# CM4_MotherBoard.net
KiCad netlist of a schematic drawn in Altium Designer
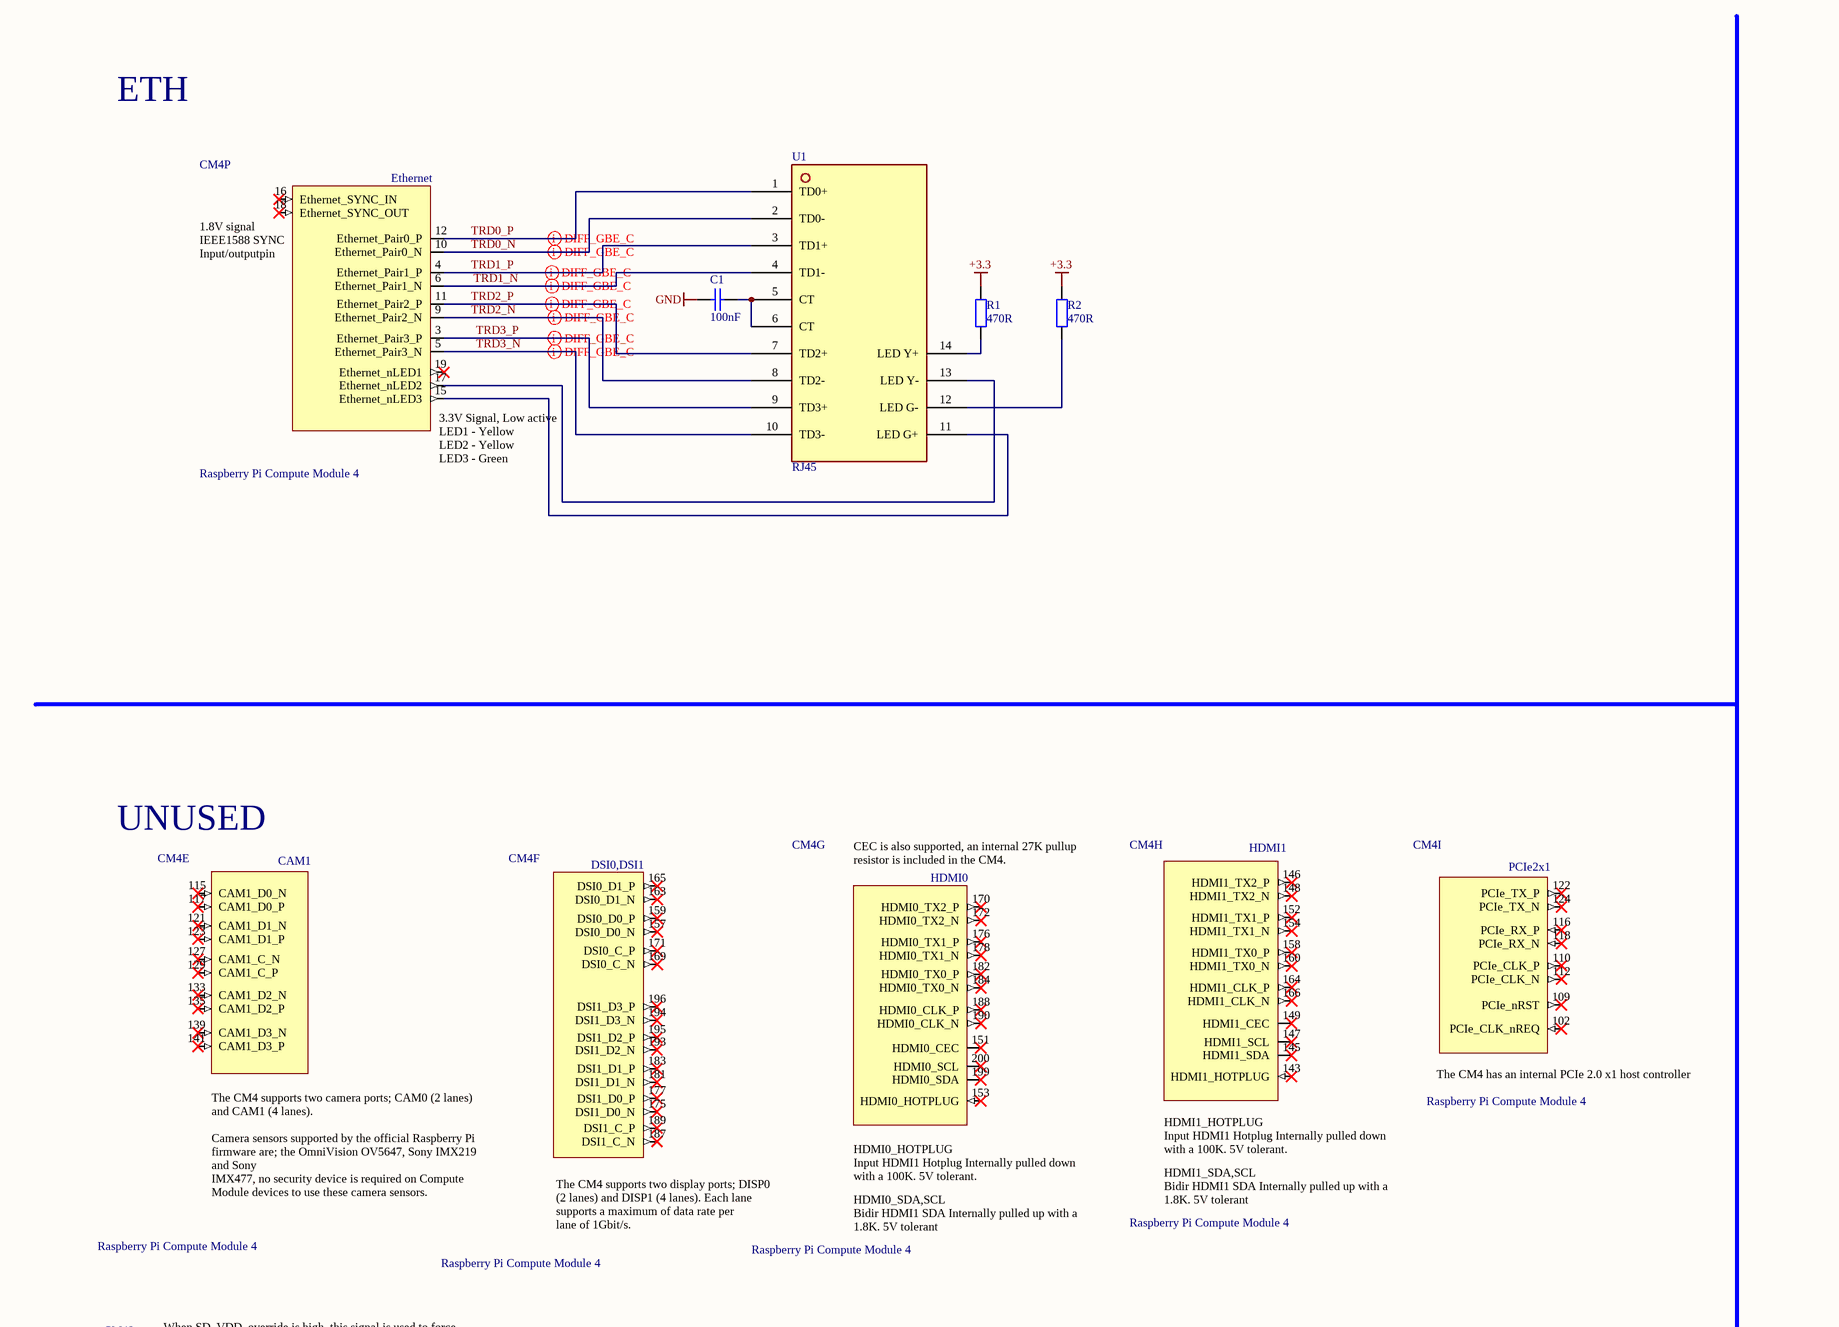
[diagram p0: CM4_MotherBoard.SchDoc, top left]
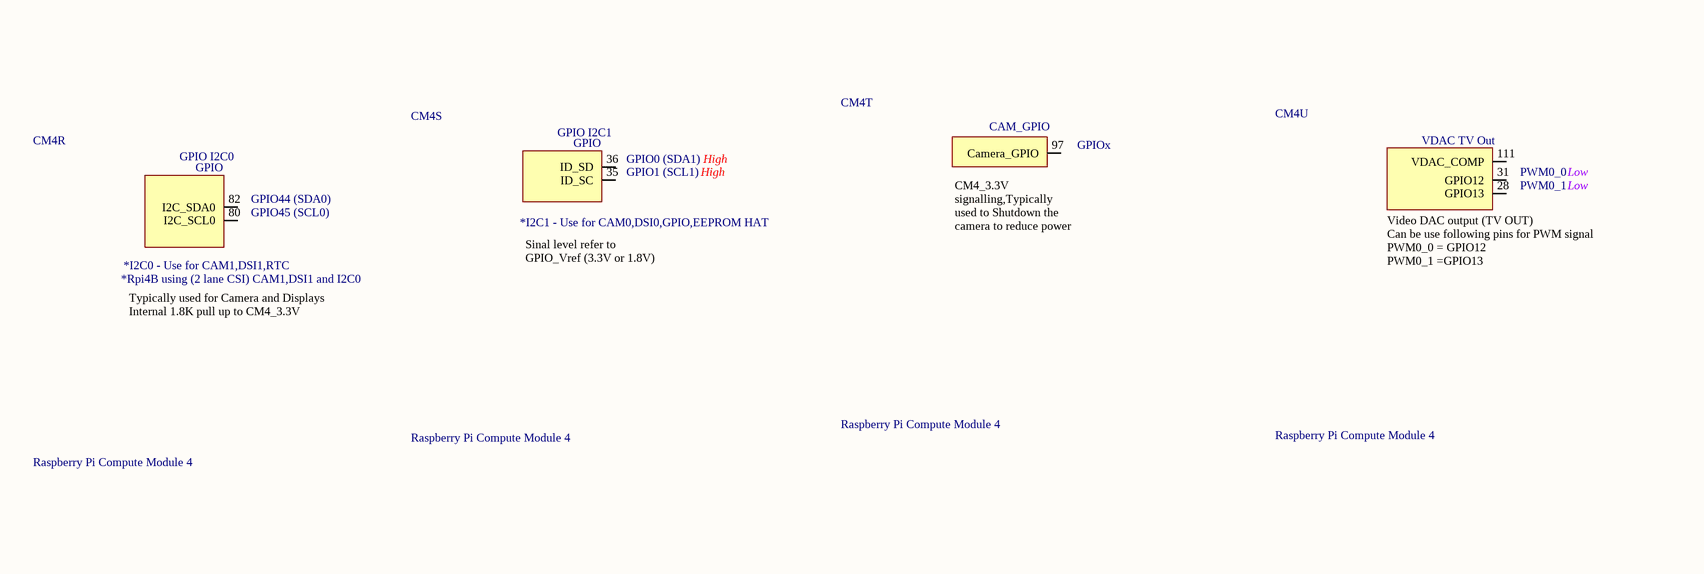
[diagram p1: CM4_MotherBoard.SchDoc, top middle]
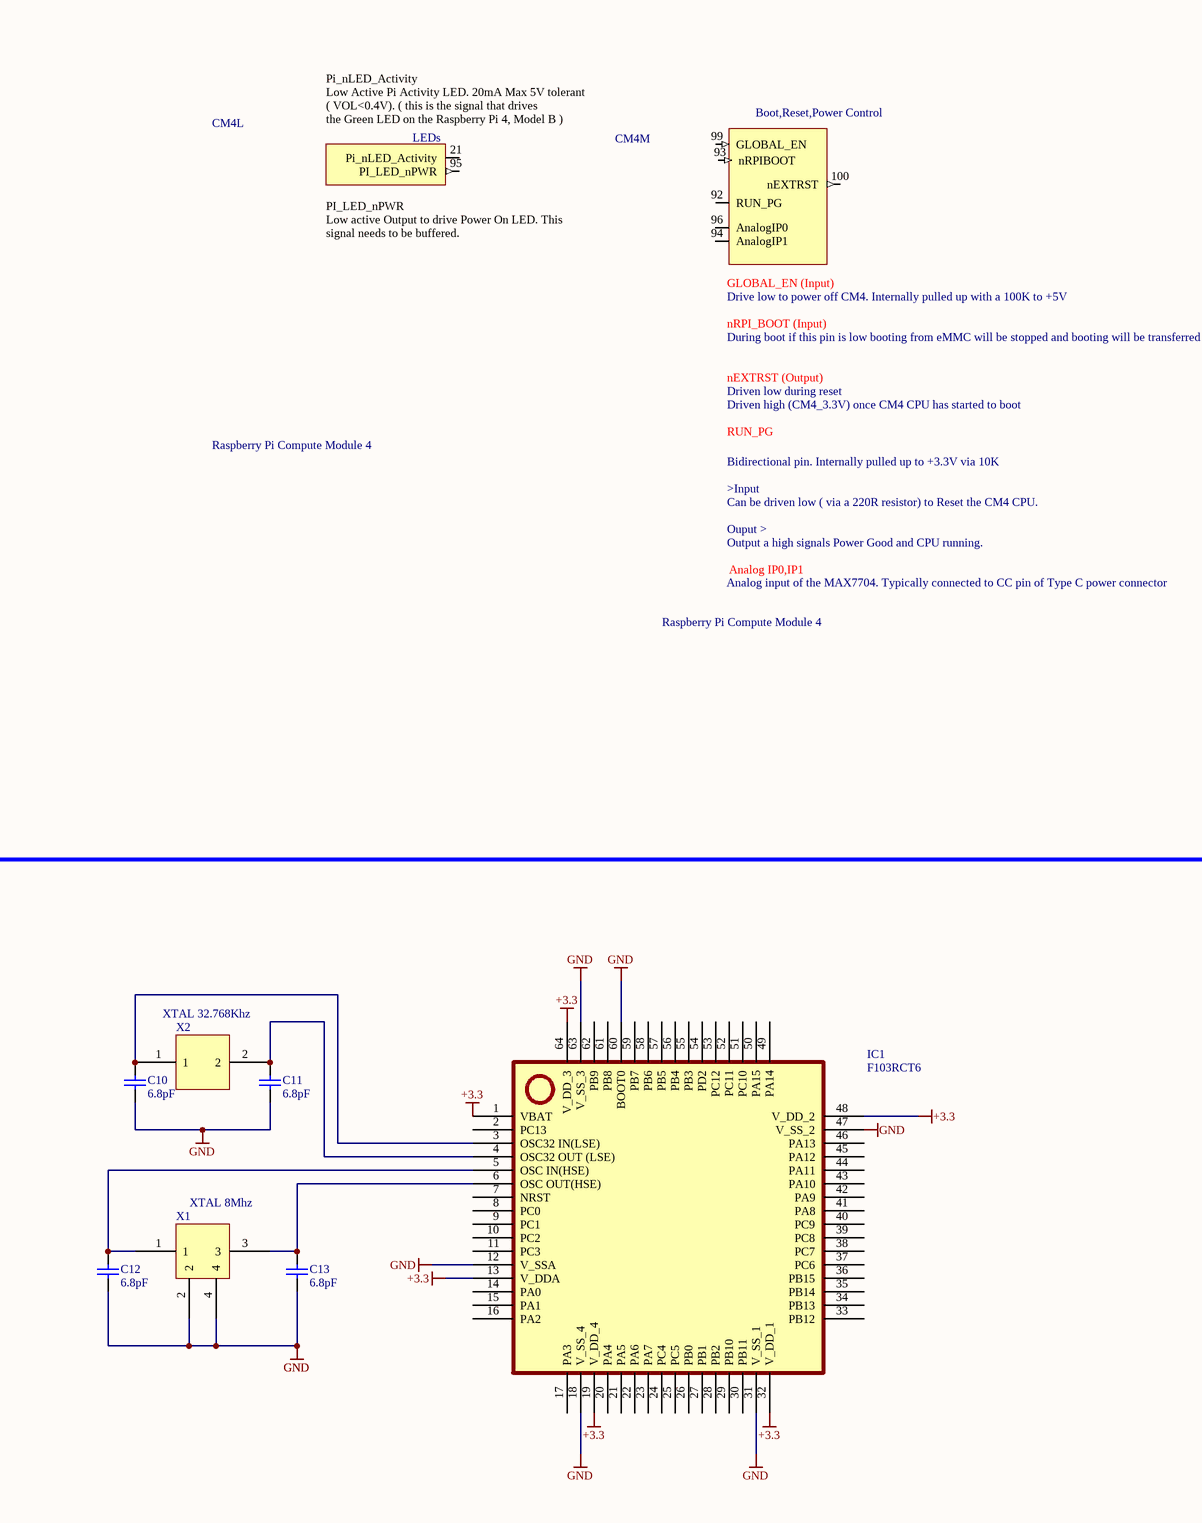
[diagram p2: CM4_MotherBoard.SchDoc, top right]
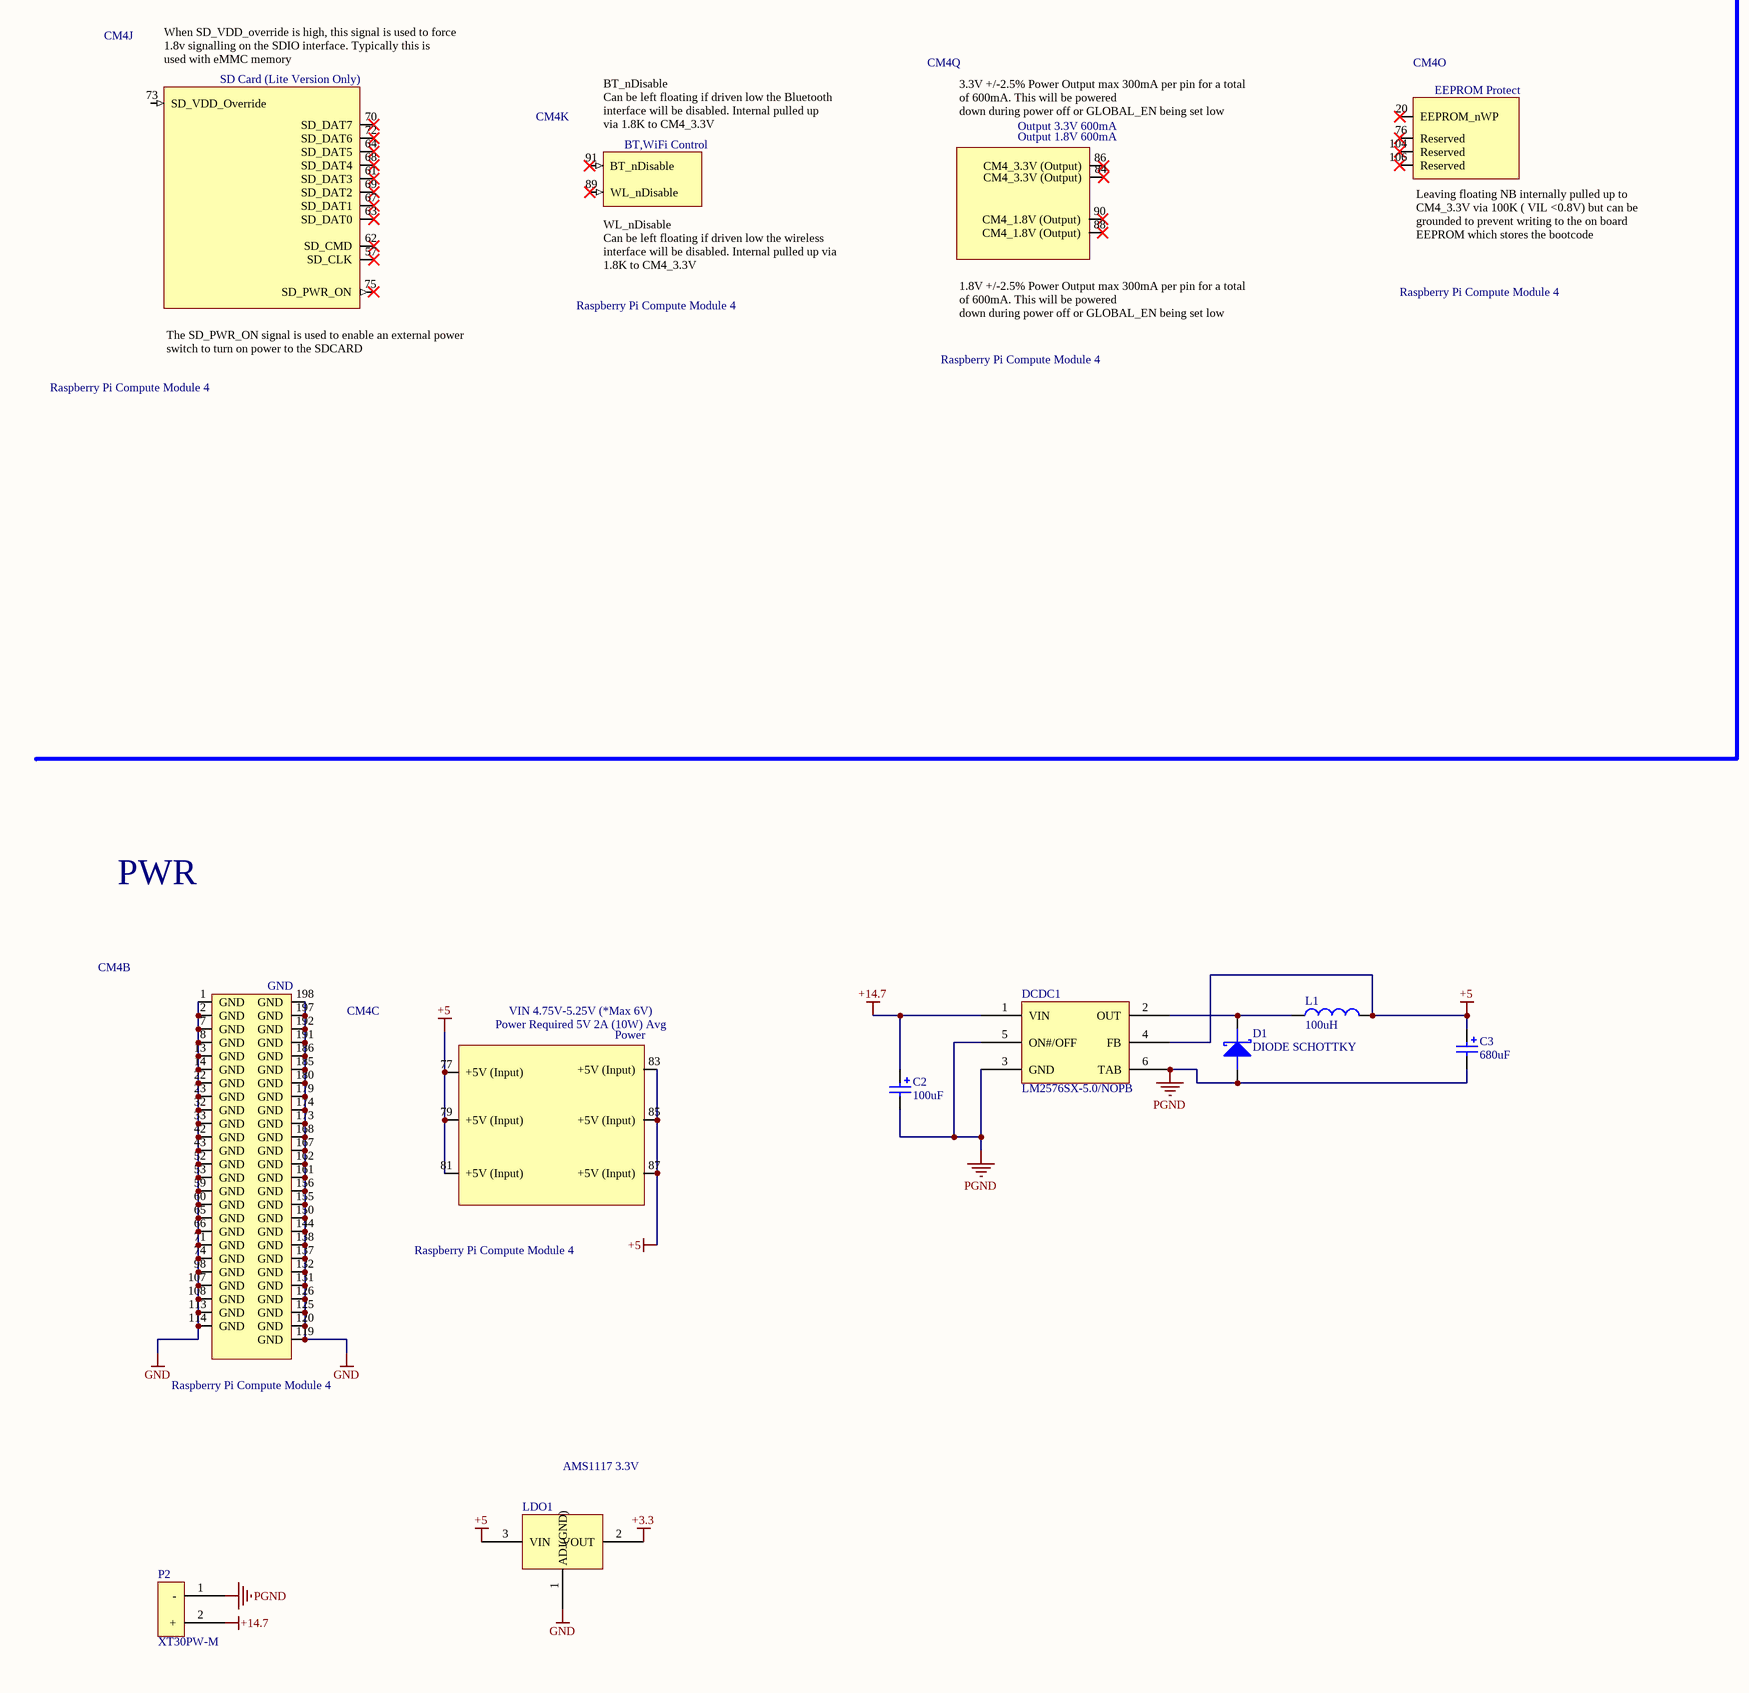
[diagram p3: CM4_MotherBoard.SchDoc, bottom left]
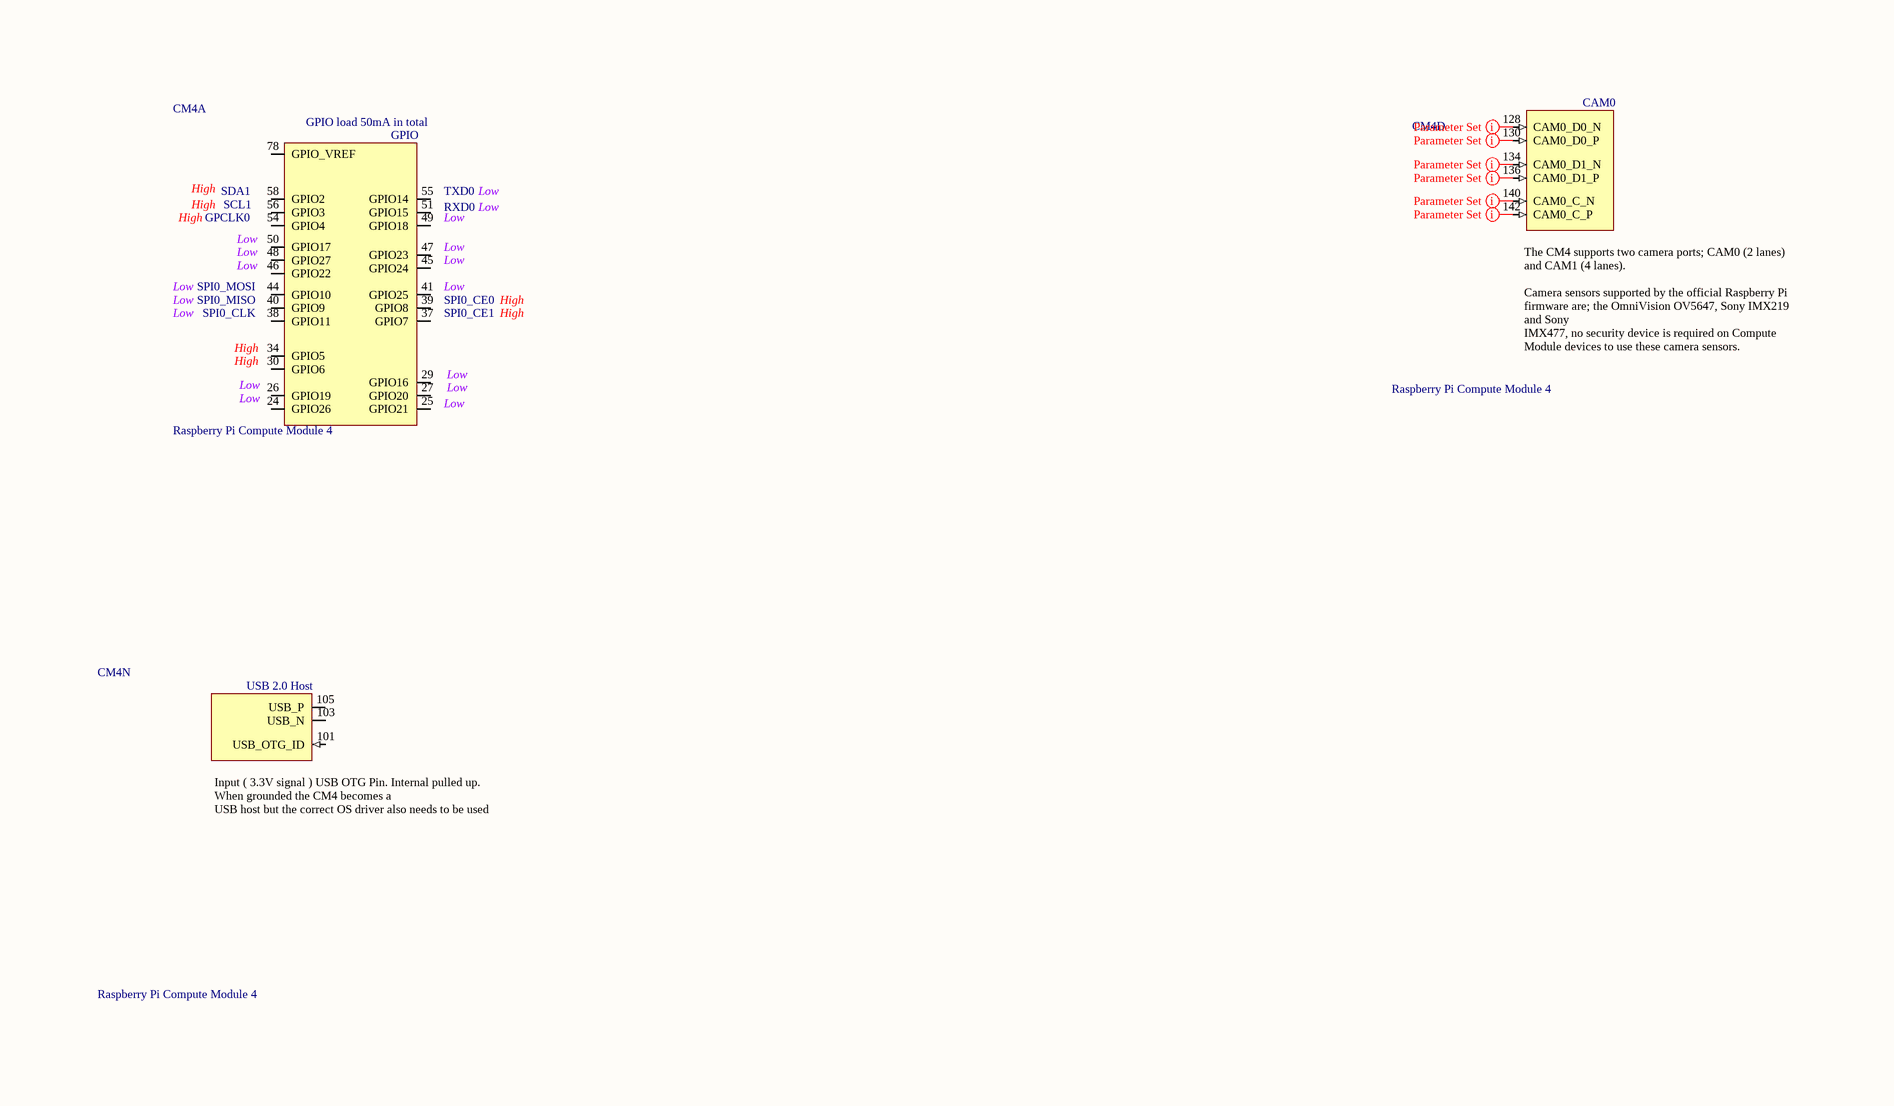
[diagram p4: CM4_MotherBoard.SchDoc, bottom middle]
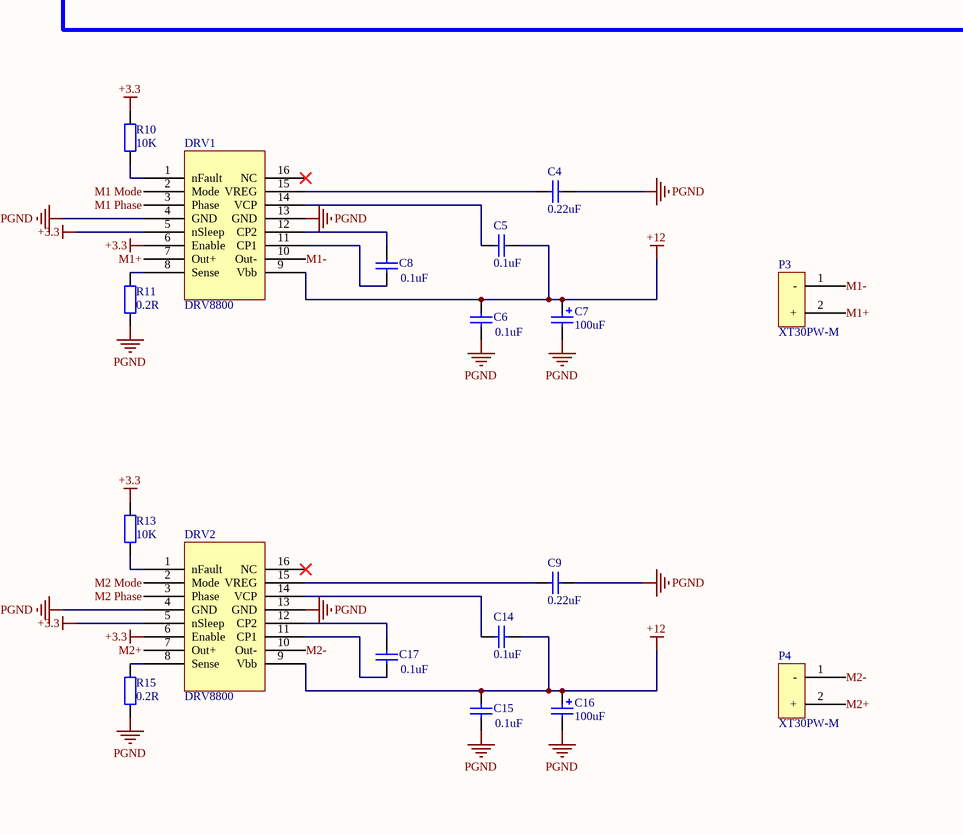
[diagram p5: CM4_MotherBoard.SchDoc, bottom right]

(export (version "E")
  (design (tool "Eeschema 10.0.6"))
  (components
    (comp (ref "C1")
      (value "100nF")
      (footprint "0805")
      (description "Capacitor")
      (fields (field (name "PUBLISHER") "Altium Limited"))
      (libsource (lib "CM4_Board") (part "Cap"))
    )
    (comp (ref "C2")
      (value "100uF")
      (footprint "Cap Pol 100uF")
      (description "Polarized Capacitor (Radial)")
      (fields (field (name "PUBLISHER") "Altium Limited"))
      (libsource (lib "CM4_Board") (part "Cap Pol"))
    )
    (comp (ref "C3")
      (value "680uF")
      (footprint "Cap Pol 680uF")
      (description "Polarized Capacitor (Radial)")
      (fields (field (name "PUBLISHER") "Altium Limited"))
      (libsource (lib "CM4_Board") (part "Cap Pol"))
    )
    (comp (ref "C4")
      (value "0.22uF")
      (footprint "0805")
      (description "Capacitor")
      (fields (field (name "PUBLISHER") "Altium Limited"))
      (libsource (lib "CM4_Board") (part "Cap"))
    )
    (comp (ref "C5")
      (value "0.1uF")
      (footprint "0805")
      (description "Capacitor")
      (fields (field (name "PUBLISHER") "Altium Limited"))
      (libsource (lib "CM4_Board") (part "Cap"))
    )
    (comp (ref "C6")
      (value "0.1uF")
      (footprint "0805")
      (description "Capacitor")
      (fields (field (name "PUBLISHER") "Altium Limited"))
      (libsource (lib "CM4_Board") (part "Cap"))
    )
    (comp (ref "C7")
      (value "100uF")
      (footprint "Cap Pol 680uF")
      (description "Polarized Capacitor (Radial)")
      (fields (field (name "PUBLISHER") "Altium Limited"))
      (libsource (lib "CM4_Board") (part "Cap Pol"))
    )
    (comp (ref "C8")
      (value "0.1uF")
      (footprint "0805")
      (description "Capacitor")
      (fields (field (name "PUBLISHER") "Altium Limited"))
      (libsource (lib "CM4_Board") (part "Cap"))
    )
    (comp (ref "C9")
      (value "0.22uF")
      (footprint "0805")
      (description "Capacitor")
      (fields (field (name "PUBLISHER") "Altium Limited"))
      (libsource (lib "CM4_Board") (part "Cap"))
    )
    (comp (ref "C10")
      (value "6.8pF")
      (footprint "0805")
      (description "Capacitor")
      (fields (field (name "PUBLISHER") "Altium Limited"))
      (libsource (lib "CM4_Board") (part "Cap"))
    )
    (comp (ref "C11")
      (value "6.8pF")
      (footprint "0805")
      (description "Capacitor")
      (fields (field (name "PUBLISHER") "Altium Limited"))
      (libsource (lib "CM4_Board") (part "Cap"))
    )
    (comp (ref "C12")
      (value "6.8pF")
      (footprint "0805")
      (description "Capacitor")
      (fields (field (name "PUBLISHER") "Altium Limited"))
      (libsource (lib "CM4_Board") (part "Cap"))
    )
    (comp (ref "C13")
      (value "6.8pF")
      (footprint "0805")
      (description "Capacitor")
      (fields (field (name "PUBLISHER") "Altium Limited"))
      (libsource (lib "CM4_Board") (part "Cap"))
    )
    (comp (ref "C14")
      (value "0.1uF")
      (footprint "0805")
      (description "Capacitor")
      (fields (field (name "PUBLISHER") "Altium Limited"))
      (libsource (lib "CM4_Board") (part "Cap"))
    )
    (comp (ref "C15")
      (value "0.1uF")
      (footprint "0805")
      (description "Capacitor")
      (fields (field (name "PUBLISHER") "Altium Limited"))
      (libsource (lib "CM4_Board") (part "Cap"))
    )
    (comp (ref "C16")
      (value "100uF")
      (footprint "Cap Pol 680uF")
      (description "Polarized Capacitor (Radial)")
      (fields (field (name "PUBLISHER") "Altium Limited"))
      (libsource (lib "CM4_Board") (part "Cap Pol"))
    )
    (comp (ref "C17")
      (value "0.1uF")
      (footprint "0805")
      (description "Capacitor")
      (fields (field (name "PUBLISHER") "Altium Limited"))
      (libsource (lib "CM4_Board") (part "Cap"))
    )
    (comp (ref "CM4")
      (value "Raspberry Pi Compute Module 4")
      (footprint "CM4-F40C-100DS-0.4v_1.5mm_0mm")
      (description "Raspberry Pi Compute Module 4 by Amornthep Phunsin")
      (libsource (lib "CM4") (part "CM4"))
    )
    (comp (ref "D1")
      (value "DIODE SCHOTTKY")
      (footprint "Schottky")
      (description "肖特基二极管")
      (libsource (lib "CM4_Board") (part "DIODE SCHOTTKY"))
    )
    (comp (ref "DCDC1")
      (value "LM2576SX-5.0/NOPB")
      (footprint "LM2576SX-5.0/NOPB")
      (libsource (lib "CM4_Board") (part "LM2576SX-5.0/NOPB"))
    )
    (comp (ref "DRV1") (value "DRV8800") (footprint "DRV8800") (libsource (lib "CM4_Board") (part "DRV8800")))
    (comp (ref "DRV2") (value "DRV8800") (footprint "DRV8800") (libsource (lib "CM4_Board") (part "DRV8800")))
    (comp (ref "IC1")
      (value "F103RCT6")
      (footprint "F103")
      (description "STM32F103RCT6 LQFP64")
      (libsource (lib "F103_Board") (part "F103RCT6"))
    )
    (comp (ref "L1")
      (value "100uH")
      (footprint "Inductor 100uH")
      (description "Inductor")
      (fields (field (name "PUBLISHER") "Altium Limited"))
      (libsource (lib "CM4_Board") (part "Inductor"))
    )
    (comp (ref "LDO1")
      (value "AMS1117 3.3V")
      (footprint "AMS117")
      (libsource (lib "CM4_Board") (part "AMS1117 3.3V"))
    )
    (comp (ref "P2")
      (value "XT30PW-M")
      (footprint "XT30PW-M")
      (libsource (lib "CM4_Board") (part "XT30PW-M"))
    )
    (comp (ref "P3")
      (value "XT30PW-M")
      (footprint "XT30PW-M")
      (libsource (lib "CM4_Board") (part "XT30PW-M"))
    )
    (comp (ref "P4")
      (value "XT30PW-M")
      (footprint "XT30PW-M")
      (libsource (lib "CM4_Board") (part "XT30PW-M"))
    )
    (comp (ref "R1")
      (value "470R")
      (footprint "0805")
      (description "Resistor")
      (fields (field (name "PUBLISHER") "Altium Limited"))
      (libsource (lib "CM4_Board") (part "Res"))
    )
    (comp (ref "R2")
      (value "470R")
      (footprint "0805")
      (description "Resistor")
      (fields (field (name "PUBLISHER") "Altium Limited"))
      (libsource (lib "CM4_Board") (part "Res"))
    )
    (comp (ref "R10")
      (value "10K")
      (footprint "0805")
      (description "Resistor")
      (fields (field (name "PUBLISHER") "Altium Limited"))
      (libsource (lib "CM4_Board") (part "Res"))
    )
    (comp (ref "R11")
      (value "0.2R")
      (footprint "0805")
      (description "Resistor")
      (fields (field (name "PUBLISHER") "Altium Limited"))
      (libsource (lib "CM4_Board") (part "Res"))
    )
    (comp (ref "R13")
      (value "10K")
      (footprint "0805")
      (description "Resistor")
      (fields (field (name "PUBLISHER") "Altium Limited"))
      (libsource (lib "CM4_Board") (part "Res"))
    )
    (comp (ref "R15")
      (value "0.2R")
      (footprint "0805")
      (description "Resistor")
      (fields (field (name "PUBLISHER") "Altium Limited"))
      (libsource (lib "CM4_Board") (part "Res"))
    )
    (comp (ref "U1")
      (value "RJ45")
      (footprint "RJ45")
      (description "48F-01GY2DPL2NL")
      (libsource (lib "CM4_Board") (part "RJ45"))
    )
    (comp (ref "X1")
      (value "XTAL 8Mhz")
      (footprint "XTAL 8Mhz")
      (description "8Mhz XTAL  SMD3225-4P")
      (libsource (lib "F103_Board") (part "XTAL 8Mhz"))
    )
    (comp (ref "X2")
      (value "XTAL 32.768Khz")
      (footprint "XTAL 32.768Khz")
      (description "32.768Khz XTAL  SMD3215-2P")
      (libsource (lib "F103_Board") (part "XTAL 32.768Khz"))
    )
  )
  (nets
    (net (code "1") (name "+3.3") (class "Default")
      (node (ref "DRV1") (pin "5") (pinfunction "nSleep_5") (pintype "passive"))
      (node (ref "DRV1") (pin "6") (pinfunction "Enable_6") (pintype "passive"))
      (node (ref "DRV2") (pin "5") (pinfunction "nSleep_5") (pintype "passive"))
      (node (ref "DRV2") (pin "6") (pinfunction "Enable_6") (pintype "passive"))
      (node (ref "IC1") (pin "1") (pinfunction "VBAT_1") (pintype "passive"))
      (node (ref "IC1") (pin "13") (pinfunction "V_DDA_13") (pintype "passive"))
      (node (ref "IC1") (pin "19") (pinfunction "V_DD_4_19") (pintype "passive"))
      (node (ref "IC1") (pin "32") (pinfunction "V_DD_1_32") (pintype "passive"))
      (node (ref "IC1") (pin "48") (pinfunction "V_DD_2_48") (pintype "passive"))
      (node (ref "IC1") (pin "64") (pinfunction "V_DD_3_64") (pintype "passive"))
      (node (ref "LDO1") (pin "2") (pinfunction "VOUT_2") (pintype "passive"))
      (node (ref "R1") (pin "2") (pinfunction "2_2") (pintype "passive"))
      (node (ref "R10") (pin "2") (pinfunction "2_2") (pintype "passive"))
      (node (ref "R13") (pin "2") (pinfunction "2_2") (pintype "passive"))
      (node (ref "R2") (pin "2") (pinfunction "2_2") (pintype "passive"))
    )
    (net (code "2") (name "+5") (class "Default")
      (node (ref "C3") (pin "1") (pinfunction "1_1") (pintype "passive"))
      (node (ref "CM4") (pin "77") (pinfunction "+5V_(Input)_77") (pintype "power_in"))
      (node (ref "CM4") (pin "79") (pinfunction "+5V_(Input)_79") (pintype "power_in"))
      (node (ref "CM4") (pin "81") (pinfunction "+5V_(Input)_81") (pintype "power_in"))
      (node (ref "CM4") (pin "83") (pinfunction "+5V_(Input)_83") (pintype "power_in"))
      (node (ref "CM4") (pin "85") (pinfunction "+5V_(Input)_85") (pintype "power_in"))
      (node (ref "CM4") (pin "87") (pinfunction "+5V_(Input)_87") (pintype "power_in"))
      (node (ref "DCDC1") (pin "4") (pinfunction "FB_4") (pintype "passive"))
      (node (ref "L1") (pin "2") (pinfunction "2_2") (pintype "passive"))
      (node (ref "LDO1") (pin "3") (pinfunction "VIN_3") (pintype "passive"))
    )
    (net (code "3") (name "+12") (class "Default")
      (node (ref "C14") (pin "2") (pinfunction "2_2") (pintype "passive"))
      (node (ref "C15") (pin "2") (pinfunction "2_2") (pintype "passive"))
      (node (ref "C16") (pin "1") (pinfunction "1_1") (pintype "passive"))
      (node (ref "C5") (pin "2") (pinfunction "2_2") (pintype "passive"))
      (node (ref "C6") (pin "2") (pinfunction "2_2") (pintype "passive"))
      (node (ref "C7") (pin "1") (pinfunction "1_1") (pintype "passive"))
      (node (ref "DRV1") (pin "9") (pinfunction "Vbb_9") (pintype "passive"))
      (node (ref "DRV2") (pin "9") (pinfunction "Vbb_9") (pintype "passive"))
    )
    (net (code "4") (name "+14.7") (class "Default")
      (node (ref "C2") (pin "1") (pinfunction "1_1") (pintype "passive"))
      (node (ref "DCDC1") (pin "1") (pinfunction "VIN_1") (pintype "passive"))
      (node (ref "P2") (pin "2") (pinfunction "+_2") (pintype "passive"))
    )
    (net (code "5") (name "/M1 Mode") (class "Default")
      (node (ref "DRV1") (pin "2") (pinfunction "Mode_2") (pintype "passive"))
    )
    (net (code "6") (name "/M1 Phase") (class "Default")
      (node (ref "DRV1") (pin "3") (pinfunction "Phase_3") (pintype "passive"))
    )
    (net (code "7") (name "/M1+") (class "Default")
      (node (ref "DRV1") (pin "7") (pinfunction "Out+_7") (pintype "passive"))
      (node (ref "P3") (pin "2") (pinfunction "+_2") (pintype "passive"))
    )
    (net (code "8") (name "/M1-") (class "Default")
      (node (ref "DRV1") (pin "10") (pinfunction "Out-_10") (pintype "passive"))
      (node (ref "P3") (pin "1") (pinfunction "-_1") (pintype "passive"))
    )
    (net (code "9") (name "/M2 Mode") (class "Default")
      (node (ref "DRV2") (pin "2") (pinfunction "Mode_2") (pintype "passive"))
    )
    (net (code "10") (name "/M2 Phase") (class "Default")
      (node (ref "DRV2") (pin "3") (pinfunction "Phase_3") (pintype "passive"))
    )
    (net (code "11") (name "/M2+") (class "Default")
      (node (ref "DRV2") (pin "7") (pinfunction "Out+_7") (pintype "passive"))
      (node (ref "P4") (pin "2") (pinfunction "+_2") (pintype "passive"))
    )
    (net (code "12") (name "/M2-") (class "Default")
      (node (ref "DRV2") (pin "10") (pinfunction "Out-_10") (pintype "passive"))
      (node (ref "P4") (pin "1") (pinfunction "-_1") (pintype "passive"))
    )
    (net (code "13") (name "/TRD0_N") (class "Default")
      (node (ref "CM4") (pin "10") (pinfunction "Ethernet_Pair0_N_10") (pintype "passive"))
      (node (ref "U1") (pin "2") (pinfunction "TD0-_2") (pintype "passive"))
    )
    (net (code "14") (name "/TRD0_P") (class "Default")
      (node (ref "CM4") (pin "12") (pinfunction "Ethernet_Pair0_P_12") (pintype "passive"))
      (node (ref "U1") (pin "1") (pinfunction "TD0+_1") (pintype "passive"))
    )
    (net (code "15") (name "/TRD1_N") (class "Default")
      (node (ref "CM4") (pin "6") (pinfunction "Ethernet_Pair1_N_6") (pintype "passive"))
      (node (ref "U1") (pin "4") (pinfunction "TD1-_4") (pintype "passive"))
    )
    (net (code "16") (name "/TRD1_P") (class "Default")
      (node (ref "CM4") (pin "4") (pinfunction "Ethernet_Pair1_P_4") (pintype "passive"))
      (node (ref "U1") (pin "3") (pinfunction "TD1+_3") (pintype "passive"))
    )
    (net (code "17") (name "/TRD2_N") (class "Default")
      (node (ref "CM4") (pin "9") (pinfunction "Ethernet_Pair2_N_9") (pintype "passive"))
      (node (ref "U1") (pin "8") (pinfunction "TD2-_8") (pintype "passive"))
    )
    (net (code "18") (name "/TRD2_P") (class "Default")
      (node (ref "CM4") (pin "11") (pinfunction "Ethernet_Pair2_P_11") (pintype "passive"))
      (node (ref "U1") (pin "7") (pinfunction "TD2+_7") (pintype "passive"))
    )
    (net (code "19") (name "/TRD3_N") (class "Default")
      (node (ref "CM4") (pin "5") (pinfunction "Ethernet_Pair3_N_5") (pintype "passive"))
      (node (ref "U1") (pin "10") (pinfunction "TD3-_10") (pintype "passive"))
    )
    (net (code "20") (name "/TRD3_P") (class "Default")
      (node (ref "CM4") (pin "3") (pinfunction "Ethernet_Pair3_P_3") (pintype "passive"))
      (node (ref "U1") (pin "9") (pinfunction "TD3+_9") (pintype "passive"))
    )
    (net (code "21") (name "GND") (class "Default")
      (node (ref "C1") (pin "1") (pinfunction "1_1") (pintype "passive"))
      (node (ref "C10") (pin "1") (pinfunction "1_1") (pintype "passive"))
      (node (ref "C11") (pin "1") (pinfunction "1_1") (pintype "passive"))
      (node (ref "C12") (pin "1") (pinfunction "1_1") (pintype "passive"))
      (node (ref "C13") (pin "1") (pinfunction "1_1") (pintype "passive"))
      (node (ref "CM4") (pin "1") (pinfunction "GND_1") (pintype "power_in"))
      (node (ref "CM4") (pin "107") (pinfunction "GND_107") (pintype "power_in"))
      (node (ref "CM4") (pin "108") (pinfunction "GND_108") (pintype "power_in"))
      (node (ref "CM4") (pin "113") (pinfunction "GND_113") (pintype "power_in"))
      (node (ref "CM4") (pin "114") (pinfunction "GND_114") (pintype "power_in"))
      (node (ref "CM4") (pin "119") (pinfunction "GND_119") (pintype "power_in"))
      (node (ref "CM4") (pin "120") (pinfunction "GND_120") (pintype "power_in"))
      (node (ref "CM4") (pin "125") (pinfunction "GND_125") (pintype "power_in"))
      (node (ref "CM4") (pin "126") (pinfunction "GND_126") (pintype "power_in"))
      (node (ref "CM4") (pin "13") (pinfunction "GND_13") (pintype "power_in"))
      (node (ref "CM4") (pin "131") (pinfunction "GND_131") (pintype "power_in"))
      (node (ref "CM4") (pin "132") (pinfunction "GND_132") (pintype "power_in"))
      (node (ref "CM4") (pin "137") (pinfunction "GND_137") (pintype "power_in"))
      (node (ref "CM4") (pin "138") (pinfunction "GND_138") (pintype "power_in"))
      (node (ref "CM4") (pin "14") (pinfunction "GND_14") (pintype "power_in"))
      (node (ref "CM4") (pin "144") (pinfunction "GND_144") (pintype "power_in"))
      (node (ref "CM4") (pin "150") (pinfunction "GND_150") (pintype "power_in"))
      (node (ref "CM4") (pin "155") (pinfunction "GND_155") (pintype "power_in"))
      (node (ref "CM4") (pin "156") (pinfunction "GND_156") (pintype "power_in"))
      (node (ref "CM4") (pin "161") (pinfunction "GND_161") (pintype "power_in"))
      (node (ref "CM4") (pin "162") (pinfunction "GND_162") (pintype "power_in"))
      (node (ref "CM4") (pin "167") (pinfunction "GND_167") (pintype "power_in"))
      (node (ref "CM4") (pin "168") (pinfunction "GND_168") (pintype "power_in"))
      (node (ref "CM4") (pin "173") (pinfunction "GND_173") (pintype "power_in"))
      (node (ref "CM4") (pin "174") (pinfunction "GND_174") (pintype "power_in"))
      (node (ref "CM4") (pin "179") (pinfunction "GND_179") (pintype "power_in"))
      (node (ref "CM4") (pin "180") (pinfunction "GND_180") (pintype "power_in"))
      (node (ref "CM4") (pin "185") (pinfunction "GND_185") (pintype "power_in"))
      (node (ref "CM4") (pin "186") (pinfunction "GND_186") (pintype "power_in"))
      (node (ref "CM4") (pin "191") (pinfunction "GND_191") (pintype "power_in"))
      (node (ref "CM4") (pin "192") (pinfunction "GND_192") (pintype "power_in"))
      (node (ref "CM4") (pin "197") (pinfunction "GND_197") (pintype "power_in"))
      (node (ref "CM4") (pin "198") (pinfunction "GND_198") (pintype "power_in"))
      (node (ref "CM4") (pin "2") (pinfunction "GND_2") (pintype "power_in"))
      (node (ref "CM4") (pin "22") (pinfunction "GND_22") (pintype "power_in"))
      (node (ref "CM4") (pin "23") (pinfunction "GND_23") (pintype "power_in"))
      (node (ref "CM4") (pin "32") (pinfunction "GND_32") (pintype "power_in"))
      (node (ref "CM4") (pin "33") (pinfunction "GND_33") (pintype "power_in"))
      (node (ref "CM4") (pin "42") (pinfunction "GND_42") (pintype "power_in"))
      (node (ref "CM4") (pin "43") (pinfunction "GND_43") (pintype "power_in"))
      (node (ref "CM4") (pin "52") (pinfunction "GND_52") (pintype "power_in"))
      (node (ref "CM4") (pin "53") (pinfunction "GND_53") (pintype "power_in"))
      (node (ref "CM4") (pin "59") (pinfunction "GND_59") (pintype "power_in"))
      (node (ref "CM4") (pin "60") (pinfunction "GND_60") (pintype "power_in"))
      (node (ref "CM4") (pin "65") (pinfunction "GND_65") (pintype "power_in"))
      (node (ref "CM4") (pin "66") (pinfunction "GND_66") (pintype "power_in"))
      (node (ref "CM4") (pin "7") (pinfunction "GND_7") (pintype "power_in"))
      (node (ref "CM4") (pin "71") (pinfunction "GND_71") (pintype "power_in"))
      (node (ref "CM4") (pin "74") (pinfunction "GND_74") (pintype "power_in"))
      (node (ref "CM4") (pin "8") (pinfunction "GND_8") (pintype "power_in"))
      (node (ref "CM4") (pin "98") (pinfunction "GND_98") (pintype "power_in"))
      (node (ref "IC1") (pin "12") (pinfunction "V_SSA_12") (pintype "passive"))
      (node (ref "IC1") (pin "18") (pinfunction "V_SS_4_18") (pintype "passive"))
      (node (ref "IC1") (pin "31") (pinfunction "V_SS_1_31") (pintype "passive"))
      (node (ref "IC1") (pin "47") (pinfunction "V_SS_2_47") (pintype "passive"))
      (node (ref "IC1") (pin "60") (pinfunction "BOOT0_60") (pintype "passive"))
      (node (ref "IC1") (pin "63") (pinfunction "V_SS_3_63") (pintype "passive"))
      (node (ref "LDO1") (pin "1") (pinfunction "ADJ(GND)_1") (pintype "passive"))
      (node (ref "X1") (pin "2") (pinfunction "2_2") (pintype "passive"))
      (node (ref "X1") (pin "4") (pinfunction "4_4") (pintype "passive"))
    )
    (net (code "22") (name "Net-(C1-Pad2)") (class "Default")
      (node (ref "C1") (pin "2") (pinfunction "2_2") (pintype "passive"))
      (node (ref "U1") (pin "5") (pinfunction "CT_5") (pintype "passive"))
      (node (ref "U1") (pin "6") (pinfunction "CT_6") (pintype "passive"))
    )
    (net (code "23") (name "Net-(CM4P-Ethernet_nLED2)") (class "Default")
      (node (ref "CM4") (pin "17") (pinfunction "Ethernet_nLED2_17") (pintype "output"))
      (node (ref "U1") (pin "13") (pinfunction "LED_Y-_13") (pintype "passive"))
    )
    (net (code "24") (name "Net-(CM4P-Ethernet_nLED3)") (class "Default")
      (node (ref "CM4") (pin "15") (pinfunction "Ethernet_nLED3_15") (pintype "output"))
      (node (ref "U1") (pin "11") (pinfunction "LED_G+_11") (pintype "passive"))
    )
    (net (code "25") (name "Net-(DCDC1-OUT)") (class "Default")
      (node (ref "D1") (pin "2") (pinfunction "2_2") (pintype "passive"))
      (node (ref "DCDC1") (pin "2") (pinfunction "OUT_2") (pintype "passive"))
      (node (ref "L1") (pin "1") (pinfunction "1_1") (pintype "passive"))
    )
    (net (code "26") (name "Net-(DRV1-CP1)") (class "Default")
      (node (ref "C8") (pin "1") (pinfunction "1_1") (pintype "passive"))
      (node (ref "DRV1") (pin "11") (pinfunction "CP1_11") (pintype "passive"))
    )
    (net (code "27") (name "Net-(DRV1-CP2)") (class "Default")
      (node (ref "C8") (pin "2") (pinfunction "2_2") (pintype "passive"))
      (node (ref "DRV1") (pin "12") (pinfunction "CP2_12") (pintype "passive"))
    )
    (net (code "28") (name "Net-(DRV1-Sense)") (class "Default")
      (node (ref "DRV1") (pin "8") (pinfunction "Sense_8") (pintype "passive"))
      (node (ref "R11") (pin "2") (pinfunction "2_2") (pintype "passive"))
    )
    (net (code "29") (name "Net-(DRV1-VCP)") (class "Default")
      (node (ref "C5") (pin "1") (pinfunction "1_1") (pintype "passive"))
      (node (ref "DRV1") (pin "14") (pinfunction "VCP_14") (pintype "passive"))
    )
    (net (code "30") (name "Net-(DRV1-VREG)") (class "Default")
      (node (ref "C4") (pin "1") (pinfunction "1_1") (pintype "passive"))
      (node (ref "DRV1") (pin "15") (pinfunction "VREG_15") (pintype "passive"))
    )
    (net (code "31") (name "Net-(DRV1-nFault)") (class "Default")
      (node (ref "DRV1") (pin "1") (pinfunction "nFault_1") (pintype "passive"))
      (node (ref "R10") (pin "1") (pinfunction "1_1") (pintype "passive"))
    )
    (net (code "32") (name "Net-(DRV2-CP1)") (class "Default")
      (node (ref "C17") (pin "1") (pinfunction "1_1") (pintype "passive"))
      (node (ref "DRV2") (pin "11") (pinfunction "CP1_11") (pintype "passive"))
    )
    (net (code "33") (name "Net-(DRV2-CP2)") (class "Default")
      (node (ref "C17") (pin "2") (pinfunction "2_2") (pintype "passive"))
      (node (ref "DRV2") (pin "12") (pinfunction "CP2_12") (pintype "passive"))
    )
    (net (code "34") (name "Net-(DRV2-Sense)") (class "Default")
      (node (ref "DRV2") (pin "8") (pinfunction "Sense_8") (pintype "passive"))
      (node (ref "R15") (pin "2") (pinfunction "2_2") (pintype "passive"))
    )
    (net (code "35") (name "Net-(DRV2-VCP)") (class "Default")
      (node (ref "C14") (pin "1") (pinfunction "1_1") (pintype "passive"))
      (node (ref "DRV2") (pin "14") (pinfunction "VCP_14") (pintype "passive"))
    )
    (net (code "36") (name "Net-(DRV2-VREG)") (class "Default")
      (node (ref "C9") (pin "1") (pinfunction "1_1") (pintype "passive"))
      (node (ref "DRV2") (pin "15") (pinfunction "VREG_15") (pintype "passive"))
    )
    (net (code "37") (name "Net-(DRV2-nFault)") (class "Default")
      (node (ref "DRV2") (pin "1") (pinfunction "nFault_1") (pintype "passive"))
      (node (ref "R13") (pin "1") (pinfunction "1_1") (pintype "passive"))
    )
    (net (code "38") (name "Net-(IC1-OSC32_IN(LSE))") (class "Default")
      (node (ref "C10") (pin "2") (pinfunction "2_2") (pintype "passive"))
      (node (ref "IC1") (pin "3") (pinfunction "OSC32_IN(LSE)_3") (pintype "passive"))
      (node (ref "X2") (pin "1") (pinfunction "1_1") (pintype "passive"))
    )
    (net (code "39") (name "Net-(IC1-OSC32_OUT_(LSE))") (class "Default")
      (node (ref "C11") (pin "2") (pinfunction "2_2") (pintype "passive"))
      (node (ref "IC1") (pin "4") (pinfunction "OSC32_OUT_(LSE)_4") (pintype "passive"))
      (node (ref "X2") (pin "2") (pinfunction "2_2") (pintype "passive"))
    )
    (net (code "40") (name "Net-(IC1-OSC_IN(HSE))") (class "Default")
      (node (ref "C12") (pin "2") (pinfunction "2_2") (pintype "passive"))
      (node (ref "IC1") (pin "5") (pinfunction "OSC_IN(HSE)_5") (pintype "passive"))
      (node (ref "X1") (pin "1") (pinfunction "1_1") (pintype "passive"))
    )
    (net (code "41") (name "Net-(IC1-OSC_OUT(HSE))") (class "Default")
      (node (ref "C13") (pin "2") (pinfunction "2_2") (pintype "passive"))
      (node (ref "IC1") (pin "6") (pinfunction "OSC_OUT(HSE)_6") (pintype "passive"))
      (node (ref "X1") (pin "3") (pinfunction "3_3") (pintype "passive"))
    )
    (net (code "42") (name "Net-(U1-LED_G-)") (class "Default")
      (node (ref "R2") (pin "1") (pinfunction "1_1") (pintype "passive"))
      (node (ref "U1") (pin "12") (pinfunction "LED_G-_12") (pintype "passive"))
    )
    (net (code "43") (name "Net-(U1-LED_Y+)") (class "Default")
      (node (ref "R1") (pin "1") (pinfunction "1_1") (pintype "passive"))
      (node (ref "U1") (pin "14") (pinfunction "LED_Y+_14") (pintype "passive"))
    )
    (net (code "44") (name "PGND") (class "Default")
      (node (ref "C15") (pin "1") (pinfunction "1_1") (pintype "passive"))
      (node (ref "C16") (pin "2") (pinfunction "2_2") (pintype "passive"))
      (node (ref "C2") (pin "2") (pinfunction "2_2") (pintype "passive"))
      (node (ref "C3") (pin "2") (pinfunction "2_2") (pintype "passive"))
      (node (ref "C4") (pin "2") (pinfunction "2_2") (pintype "passive"))
      (node (ref "C6") (pin "1") (pinfunction "1_1") (pintype "passive"))
      (node (ref "C7") (pin "2") (pinfunction "2_2") (pintype "passive"))
      (node (ref "C9") (pin "2") (pinfunction "2_2") (pintype "passive"))
      (node (ref "D1") (pin "1") (pinfunction "1_1") (pintype "passive"))
      (node (ref "DCDC1") (pin "3") (pinfunction "GND_3") (pintype "passive"))
      (node (ref "DCDC1") (pin "5") (pinfunction "ON#/OFF_5") (pintype "passive"))
      (node (ref "DCDC1") (pin "6") (pinfunction "TAB_6") (pintype "passive"))
      (node (ref "DRV1") (pin "13") (pinfunction "GND_13") (pintype "passive"))
      (node (ref "DRV1") (pin "4") (pinfunction "GND_4") (pintype "passive"))
      (node (ref "DRV2") (pin "13") (pinfunction "GND_13") (pintype "passive"))
      (node (ref "DRV2") (pin "4") (pinfunction "GND_4") (pintype "passive"))
      (node (ref "P2") (pin "1") (pinfunction "-_1") (pintype "passive"))
      (node (ref "R11") (pin "1") (pinfunction "1_1") (pintype "passive"))
      (node (ref "R15") (pin "1") (pinfunction "1_1") (pintype "passive"))
    )
    (net (code "45") (name "unconnected-(CM4A-GPIO2-Pad58)") (class "Default")
      (node (ref "CM4") (pin "58") (pinfunction "GPIO2_58") (pintype "passive"))
    )
    (net (code "46") (name "unconnected-(CM4A-GPIO3-Pad56)") (class "Default")
      (node (ref "CM4") (pin "56") (pinfunction "GPIO3_56") (pintype "passive"))
    )
    (net (code "47") (name "unconnected-(CM4A-GPIO4-Pad54)") (class "Default")
      (node (ref "CM4") (pin "54") (pinfunction "GPIO4_54") (pintype "passive"))
    )
    (net (code "48") (name "unconnected-(CM4A-GPIO5-Pad34)") (class "Default")
      (node (ref "CM4") (pin "34") (pinfunction "GPIO5_34") (pintype "passive"))
    )
    (net (code "49") (name "unconnected-(CM4A-GPIO6-Pad30)") (class "Default")
      (node (ref "CM4") (pin "30") (pinfunction "GPIO6_30") (pintype "passive"))
    )
    (net (code "50") (name "unconnected-(CM4A-GPIO7-Pad37)") (class "Default")
      (node (ref "CM4") (pin "37") (pinfunction "GPIO7_37") (pintype "passive"))
    )
    (net (code "51") (name "unconnected-(CM4A-GPIO8-Pad39)") (class "Default")
      (node (ref "CM4") (pin "39") (pinfunction "GPIO8_39") (pintype "passive"))
    )
    (net (code "52") (name "unconnected-(CM4A-GPIO9-Pad40)") (class "Default")
      (node (ref "CM4") (pin "40") (pinfunction "GPIO9_40") (pintype "passive"))
    )
    (net (code "53") (name "unconnected-(CM4A-GPIO10-Pad44)") (class "Default")
      (node (ref "CM4") (pin "44") (pinfunction "GPIO10_44") (pintype "passive"))
    )
    (net (code "54") (name "unconnected-(CM4A-GPIO11-Pad38)") (class "Default")
      (node (ref "CM4") (pin "38") (pinfunction "GPIO11_38") (pintype "passive"))
    )
    (net (code "55") (name "unconnected-(CM4A-GPIO14-Pad55)") (class "Default")
      (node (ref "CM4") (pin "55") (pinfunction "GPIO14_55") (pintype "passive"))
    )
    (net (code "56") (name "unconnected-(CM4A-GPIO15-Pad51)") (class "Default")
      (node (ref "CM4") (pin "51") (pinfunction "GPIO15_51") (pintype "passive"))
    )
    (net (code "57") (name "unconnected-(CM4A-GPIO16-Pad29)") (class "Default")
      (node (ref "CM4") (pin "29") (pinfunction "GPIO16_29") (pintype "passive"))
    )
    (net (code "58") (name "unconnected-(CM4A-GPIO17-Pad50)") (class "Default")
      (node (ref "CM4") (pin "50") (pinfunction "GPIO17_50") (pintype "passive"))
    )
    (net (code "59") (name "unconnected-(CM4A-GPIO18-Pad49)") (class "Default")
      (node (ref "CM4") (pin "49") (pinfunction "GPIO18_49") (pintype "passive"))
    )
    (net (code "60") (name "unconnected-(CM4A-GPIO19-Pad26)") (class "Default")
      (node (ref "CM4") (pin "26") (pinfunction "GPIO19_26") (pintype "passive"))
    )
    (net (code "61") (name "unconnected-(CM4A-GPIO20-Pad27)") (class "Default")
      (node (ref "CM4") (pin "27") (pinfunction "GPIO20_27") (pintype "passive"))
    )
    (net (code "62") (name "unconnected-(CM4A-GPIO21-Pad25)") (class "Default")
      (node (ref "CM4") (pin "25") (pinfunction "GPIO21_25") (pintype "passive"))
    )
    (net (code "63") (name "unconnected-(CM4A-GPIO22-Pad46)") (class "Default")
      (node (ref "CM4") (pin "46") (pinfunction "GPIO22_46") (pintype "passive"))
    )
    (net (code "64") (name "unconnected-(CM4A-GPIO23-Pad47)") (class "Default")
      (node (ref "CM4") (pin "47") (pinfunction "GPIO23_47") (pintype "passive"))
    )
    (net (code "65") (name "unconnected-(CM4A-GPIO24-Pad45)") (class "Default")
      (node (ref "CM4") (pin "45") (pinfunction "GPIO24_45") (pintype "passive"))
    )
    (net (code "66") (name "unconnected-(CM4A-GPIO25-Pad41)") (class "Default")
      (node (ref "CM4") (pin "41") (pinfunction "GPIO25_41") (pintype "passive"))
    )
    (net (code "67") (name "unconnected-(CM4A-GPIO26-Pad24)") (class "Default")
      (node (ref "CM4") (pin "24") (pinfunction "GPIO26_24") (pintype "passive"))
    )
    (net (code "68") (name "unconnected-(CM4A-GPIO27-Pad48)") (class "Default")
      (node (ref "CM4") (pin "48") (pinfunction "GPIO27_48") (pintype "passive"))
    )
    (net (code "69") (name "unconnected-(CM4A-GPIO_VREF-Pad78)") (class "Default")
      (node (ref "CM4") (pin "78") (pinfunction "GPIO_VREF_78") (pintype "power_in"))
    )
    (net (code "70") (name "unconnected-(CM4D-CAM0_C_N-Pad140)") (class "Default")
      (node (ref "CM4") (pin "140") (pinfunction "CAM0_C_N_140") (pintype "input"))
    )
    (net (code "71") (name "unconnected-(CM4D-CAM0_C_P-Pad142)") (class "Default")
      (node (ref "CM4") (pin "142") (pinfunction "CAM0_C_P_142") (pintype "input"))
    )
    (net (code "72") (name "unconnected-(CM4D-CAM0_D0_N-Pad128)") (class "Default")
      (node (ref "CM4") (pin "128") (pinfunction "CAM0_D0_N_128") (pintype "input"))
    )
    (net (code "73") (name "unconnected-(CM4D-CAM0_D0_P-Pad130)") (class "Default")
      (node (ref "CM4") (pin "130") (pinfunction "CAM0_D0_P_130") (pintype "input"))
    )
    (net (code "74") (name "unconnected-(CM4D-CAM0_D1_N-Pad134)") (class "Default")
      (node (ref "CM4") (pin "134") (pinfunction "CAM0_D1_N_134") (pintype "input"))
    )
    (net (code "75") (name "unconnected-(CM4D-CAM0_D1_P-Pad136)") (class "Default")
      (node (ref "CM4") (pin "136") (pinfunction "CAM0_D1_P_136") (pintype "input"))
    )
    (net (code "76") (name "unconnected-(CM4E-CAM1_C_N-Pad127)") (class "Default")
      (node (ref "CM4") (pin "127") (pinfunction "CAM1_C_N_127") (pintype "input+no_connect"))
    )
    (net (code "77") (name "unconnected-(CM4E-CAM1_C_P-Pad129)") (class "Default")
      (node (ref "CM4") (pin "129") (pinfunction "CAM1_C_P_129") (pintype "input+no_connect"))
    )
    (net (code "78") (name "unconnected-(CM4E-CAM1_D0_N-Pad115)") (class "Default")
      (node (ref "CM4") (pin "115") (pinfunction "CAM1_D0_N_115") (pintype "input+no_connect"))
    )
    (net (code "79") (name "unconnected-(CM4E-CAM1_D0_P-Pad117)") (class "Default")
      (node (ref "CM4") (pin "117") (pinfunction "CAM1_D0_P_117") (pintype "input+no_connect"))
    )
    (net (code "80") (name "unconnected-(CM4E-CAM1_D1_N-Pad121)") (class "Default")
      (node (ref "CM4") (pin "121") (pinfunction "CAM1_D1_N_121") (pintype "input+no_connect"))
    )
    (net (code "81") (name "unconnected-(CM4E-CAM1_D1_P-Pad123)") (class "Default")
      (node (ref "CM4") (pin "123") (pinfunction "CAM1_D1_P_123") (pintype "input+no_connect"))
    )
    (net (code "82") (name "unconnected-(CM4E-CAM1_D2_N-Pad133)") (class "Default")
      (node (ref "CM4") (pin "133") (pinfunction "CAM1_D2_N_133") (pintype "input+no_connect"))
    )
    (net (code "83") (name "unconnected-(CM4E-CAM1_D2_P-Pad135)") (class "Default")
      (node (ref "CM4") (pin "135") (pinfunction "CAM1_D2_P_135") (pintype "input+no_connect"))
    )
    (net (code "84") (name "unconnected-(CM4E-CAM1_D3_N-Pad139)") (class "Default")
      (node (ref "CM4") (pin "139") (pinfunction "CAM1_D3_N_139") (pintype "input+no_connect"))
    )
    (net (code "85") (name "unconnected-(CM4E-CAM1_D3_P-Pad141)") (class "Default")
      (node (ref "CM4") (pin "141") (pinfunction "CAM1_D3_P_141") (pintype "input+no_connect"))
    )
    (net (code "86") (name "unconnected-(CM4F-DSI0_C_N-Pad169)") (class "Default")
      (node (ref "CM4") (pin "169") (pinfunction "DSI0_C_N_169") (pintype "output+no_connect"))
    )
    (net (code "87") (name "unconnected-(CM4F-DSI0_C_P-Pad171)") (class "Default")
      (node (ref "CM4") (pin "171") (pinfunction "DSI0_C_P_171") (pintype "output+no_connect"))
    )
    (net (code "88") (name "unconnected-(CM4F-DSI0_D0_N-Pad157)") (class "Default")
      (node (ref "CM4") (pin "157") (pinfunction "DSI0_D0_N_157") (pintype "output+no_connect"))
    )
    (net (code "89") (name "unconnected-(CM4F-DSI0_D0_P-Pad159)") (class "Default")
      (node (ref "CM4") (pin "159") (pinfunction "DSI0_D0_P_159") (pintype "output+no_connect"))
    )
    (net (code "90") (name "unconnected-(CM4F-DSI0_D1_N-Pad163)") (class "Default")
      (node (ref "CM4") (pin "163") (pinfunction "DSI0_D1_N_163") (pintype "output+no_connect"))
    )
    (net (code "91") (name "unconnected-(CM4F-DSI0_D1_P-Pad165)") (class "Default")
      (node (ref "CM4") (pin "165") (pinfunction "DSI0_D1_P_165") (pintype "output+no_connect"))
    )
    (net (code "92") (name "unconnected-(CM4F-DSI1_C_N-Pad187)") (class "Default")
      (node (ref "CM4") (pin "187") (pinfunction "DSI1_C_N_187") (pintype "output+no_connect"))
    )
    (net (code "93") (name "unconnected-(CM4F-DSI1_C_P-Pad189)") (class "Default")
      (node (ref "CM4") (pin "189") (pinfunction "DSI1_C_P_189") (pintype "output+no_connect"))
    )
    (net (code "94") (name "unconnected-(CM4F-DSI1_D0_N-Pad175)") (class "Default")
      (node (ref "CM4") (pin "175") (pinfunction "DSI1_D0_N_175") (pintype "output+no_connect"))
    )
    (net (code "95") (name "unconnected-(CM4F-DSI1_D0_P-Pad177)") (class "Default")
      (node (ref "CM4") (pin "177") (pinfunction "DSI1_D0_P_177") (pintype "output+no_connect"))
    )
    (net (code "96") (name "unconnected-(CM4F-DSI1_D1_N-Pad181)") (class "Default")
      (node (ref "CM4") (pin "181") (pinfunction "DSI1_D1_N_181") (pintype "output+no_connect"))
    )
    (net (code "97") (name "unconnected-(CM4F-DSI1_D1_P-Pad183)") (class "Default")
      (node (ref "CM4") (pin "183") (pinfunction "DSI1_D1_P_183") (pintype "output+no_connect"))
    )
    (net (code "98") (name "unconnected-(CM4F-DSI1_D2_N-Pad193)") (class "Default")
      (node (ref "CM4") (pin "193") (pinfunction "DSI1_D2_N_193") (pintype "output+no_connect"))
    )
    (net (code "99") (name "unconnected-(CM4F-DSI1_D2_P-Pad195)") (class "Default")
      (node (ref "CM4") (pin "195") (pinfunction "DSI1_D2_P_195") (pintype "output+no_connect"))
    )
    (net (code "100") (name "unconnected-(CM4F-DSI1_D3_N-Pad194)") (class "Default")
      (node (ref "CM4") (pin "194") (pinfunction "DSI1_D3_N_194") (pintype "output+no_connect"))
    )
    (net (code "101") (name "unconnected-(CM4F-DSI1_D3_P-Pad196)") (class "Default")
      (node (ref "CM4") (pin "196") (pinfunction "DSI1_D3_P_196") (pintype "output+no_connect"))
    )
    (net (code "102") (name "unconnected-(CM4G-HDMI0_CEC-Pad151)") (class "Default")
      (node (ref "CM4") (pin "151") (pinfunction "HDMI0_CEC_151") (pintype "open_collector+no_connect"))
    )
    (net (code "103") (name "unconnected-(CM4G-HDMI0_CLK_N-Pad190)") (class "Default")
      (node (ref "CM4") (pin "190") (pinfunction "HDMI0_CLK_N_190") (pintype "output+no_connect"))
    )
    (net (code "104") (name "unconnected-(CM4G-HDMI0_CLK_P-Pad188)") (class "Default")
      (node (ref "CM4") (pin "188") (pinfunction "HDMI0_CLK_P_188") (pintype "output+no_connect"))
    )
    (net (code "105") (name "unconnected-(CM4G-HDMI0_HOTPLUG-Pad153)") (class "Default")
      (node (ref "CM4") (pin "153") (pinfunction "HDMI0_HOTPLUG_153") (pintype "input+no_connect"))
    )
    (net (code "106") (name "unconnected-(CM4G-HDMI0_SCL-Pad200)") (class "Default")
      (node (ref "CM4") (pin "200") (pinfunction "HDMI0_SCL_200") (pintype "open_collector+no_connect"))
    )
    (net (code "107") (name "unconnected-(CM4G-HDMI0_SDA-Pad199)") (class "Default")
      (node (ref "CM4") (pin "199") (pinfunction "HDMI0_SDA_199") (pintype "bidirectional+no_connect"))
    )
    (net (code "108") (name "unconnected-(CM4G-HDMI0_TX0_N-Pad184)") (class "Default")
      (node (ref "CM4") (pin "184") (pinfunction "HDMI0_TX0_N_184") (pintype "output+no_connect"))
    )
    (net (code "109") (name "unconnected-(CM4G-HDMI0_TX0_P-Pad182)") (class "Default")
      (node (ref "CM4") (pin "182") (pinfunction "HDMI0_TX0_P_182") (pintype "output+no_connect"))
    )
    (net (code "110") (name "unconnected-(CM4G-HDMI0_TX1_N-Pad178)") (class "Default")
      (node (ref "CM4") (pin "178") (pinfunction "HDMI0_TX1_N_178") (pintype "output+no_connect"))
    )
    (net (code "111") (name "unconnected-(CM4G-HDMI0_TX1_P-Pad176)") (class "Default")
      (node (ref "CM4") (pin "176") (pinfunction "HDMI0_TX1_P_176") (pintype "output+no_connect"))
    )
    (net (code "112") (name "unconnected-(CM4G-HDMI0_TX2_N-Pad172)") (class "Default")
      (node (ref "CM4") (pin "172") (pinfunction "HDMI0_TX2_N_172") (pintype "output+no_connect"))
    )
    (net (code "113") (name "unconnected-(CM4G-HDMI0_TX2_P-Pad170)") (class "Default")
      (node (ref "CM4") (pin "170") (pinfunction "HDMI0_TX2_P_170") (pintype "output+no_connect"))
    )
    (net (code "114") (name "unconnected-(CM4H-HDMI1_CEC-Pad149)") (class "Default")
      (node (ref "CM4") (pin "149") (pinfunction "HDMI1_CEC_149") (pintype "open_collector+no_connect"))
    )
    (net (code "115") (name "unconnected-(CM4H-HDMI1_CLK_N-Pad166)") (class "Default")
      (node (ref "CM4") (pin "166") (pinfunction "HDMI1_CLK_N_166") (pintype "output+no_connect"))
    )
    (net (code "116") (name "unconnected-(CM4H-HDMI1_CLK_P-Pad164)") (class "Default")
      (node (ref "CM4") (pin "164") (pinfunction "HDMI1_CLK_P_164") (pintype "output+no_connect"))
    )
    (net (code "117") (name "unconnected-(CM4H-HDMI1_HOTPLUG-Pad143)") (class "Default")
      (node (ref "CM4") (pin "143") (pinfunction "HDMI1_HOTPLUG_143") (pintype "input+no_connect"))
    )
    (net (code "118") (name "unconnected-(CM4H-HDMI1_SCL-Pad147)") (class "Default")
      (node (ref "CM4") (pin "147") (pinfunction "HDMI1_SCL_147") (pintype "open_collector+no_connect"))
    )
    (net (code "119") (name "unconnected-(CM4H-HDMI1_SDA-Pad145)") (class "Default")
      (node (ref "CM4") (pin "145") (pinfunction "HDMI1_SDA_145") (pintype "bidirectional+no_connect"))
    )
    (net (code "120") (name "unconnected-(CM4H-HDMI1_TX0_N-Pad160)") (class "Default")
      (node (ref "CM4") (pin "160") (pinfunction "HDMI1_TX0_N_160") (pintype "output+no_connect"))
    )
    (net (code "121") (name "unconnected-(CM4H-HDMI1_TX0_P-Pad158)") (class "Default")
      (node (ref "CM4") (pin "158") (pinfunction "HDMI1_TX0_P_158") (pintype "output+no_connect"))
    )
    (net (code "122") (name "unconnected-(CM4H-HDMI1_TX1_N-Pad154)") (class "Default")
      (node (ref "CM4") (pin "154") (pinfunction "HDMI1_TX1_N_154") (pintype "output+no_connect"))
    )
    (net (code "123") (name "unconnected-(CM4H-HDMI1_TX1_P-Pad152)") (class "Default")
      (node (ref "CM4") (pin "152") (pinfunction "HDMI1_TX1_P_152") (pintype "output+no_connect"))
    )
    (net (code "124") (name "unconnected-(CM4H-HDMI1_TX2_N-Pad148)") (class "Default")
      (node (ref "CM4") (pin "148") (pinfunction "HDMI1_TX2_N_148") (pintype "output+no_connect"))
    )
    (net (code "125") (name "unconnected-(CM4H-HDMI1_TX2_P-Pad146)") (class "Default")
      (node (ref "CM4") (pin "146") (pinfunction "HDMI1_TX2_P_146") (pintype "output+no_connect"))
    )
    (net (code "126") (name "unconnected-(CM4I-PCIe_CLK_N-Pad112)") (class "Default")
      (node (ref "CM4") (pin "112") (pinfunction "PCIe_CLK_N_112") (pintype "output+no_connect"))
    )
    (net (code "127") (name "unconnected-(CM4I-PCIe_CLK_P-Pad110)") (class "Default")
      (node (ref "CM4") (pin "110") (pinfunction "PCIe_CLK_P_110") (pintype "output+no_connect"))
    )
    (net (code "128") (name "unconnected-(CM4I-PCIe_CLK_nREQ-Pad102)") (class "Default")
      (node (ref "CM4") (pin "102") (pinfunction "PCIe_CLK_nREQ_102") (pintype "input+no_connect"))
    )
    (net (code "129") (name "unconnected-(CM4I-PCIe_RX_N-Pad118)") (class "Default")
      (node (ref "CM4") (pin "118") (pinfunction "PCIe_RX_N_118") (pintype "input+no_connect"))
    )
    (net (code "130") (name "unconnected-(CM4I-PCIe_RX_P-Pad116)") (class "Default")
      (node (ref "CM4") (pin "116") (pinfunction "PCIe_RX_P_116") (pintype "input+no_connect"))
    )
    (net (code "131") (name "unconnected-(CM4I-PCIe_TX_N-Pad124)") (class "Default")
      (node (ref "CM4") (pin "124") (pinfunction "PCIe_TX_N_124") (pintype "output+no_connect"))
    )
    (net (code "132") (name "unconnected-(CM4I-PCIe_TX_P-Pad122)") (class "Default")
      (node (ref "CM4") (pin "122") (pinfunction "PCIe_TX_P_122") (pintype "output+no_connect"))
    )
    (net (code "133") (name "unconnected-(CM4I-PCIe_nRST-Pad109)") (class "Default")
      (node (ref "CM4") (pin "109") (pinfunction "PCIe_nRST_109") (pintype "output+no_connect"))
    )
    (net (code "134") (name "unconnected-(CM4J-SD_CLK-Pad57)") (class "Default")
      (node (ref "CM4") (pin "57") (pinfunction "SD_CLK_57") (pintype "passive+no_connect"))
    )
    (net (code "135") (name "unconnected-(CM4J-SD_CMD-Pad62)") (class "Default")
      (node (ref "CM4") (pin "62") (pinfunction "SD_CMD_62") (pintype "passive+no_connect"))
    )
    (net (code "136") (name "unconnected-(CM4J-SD_DAT0-Pad63)") (class "Default")
      (node (ref "CM4") (pin "63") (pinfunction "SD_DAT0_63") (pintype "passive+no_connect"))
    )
    (net (code "137") (name "unconnected-(CM4J-SD_DAT1-Pad67)") (class "Default")
      (node (ref "CM4") (pin "67") (pinfunction "SD_DAT1_67") (pintype "passive+no_connect"))
    )
    (net (code "138") (name "unconnected-(CM4J-SD_DAT2-Pad69)") (class "Default")
      (node (ref "CM4") (pin "69") (pinfunction "SD_DAT2_69") (pintype "passive+no_connect"))
    )
    (net (code "139") (name "unconnected-(CM4J-SD_DAT3-Pad61)") (class "Default")
      (node (ref "CM4") (pin "61") (pinfunction "SD_DAT3_61") (pintype "passive+no_connect"))
    )
    (net (code "140") (name "unconnected-(CM4J-SD_DAT4-Pad68)") (class "Default")
      (node (ref "CM4") (pin "68") (pinfunction "SD_DAT4_68") (pintype "passive+no_connect"))
    )
    (net (code "141") (name "unconnected-(CM4J-SD_DAT5-Pad64)") (class "Default")
      (node (ref "CM4") (pin "64") (pinfunction "SD_DAT5_64") (pintype "passive+no_connect"))
    )
    (net (code "142") (name "unconnected-(CM4J-SD_DAT6-Pad72)") (class "Default")
      (node (ref "CM4") (pin "72") (pinfunction "SD_DAT6_72") (pintype "passive+no_connect"))
    )
    (net (code "143") (name "unconnected-(CM4J-SD_DAT7-Pad70)") (class "Default")
      (node (ref "CM4") (pin "70") (pinfunction "SD_DAT7_70") (pintype "passive+no_connect"))
    )
    (net (code "144") (name "unconnected-(CM4J-SD_PWR_ON-Pad75)") (class "Default")
      (node (ref "CM4") (pin "75") (pinfunction "SD_PWR_ON_75") (pintype "output+no_connect"))
    )
    (net (code "145") (name "unconnected-(CM4J-SD_VDD_Override-Pad73)") (class "Default")
      (node (ref "CM4") (pin "73") (pinfunction "SD_VDD_Override_73") (pintype "input"))
    )
    (net (code "146") (name "unconnected-(CM4K-BT_nDisable-Pad91)") (class "Default")
      (node (ref "CM4") (pin "91") (pinfunction "BT_nDisable_91") (pintype "input+no_connect"))
    )
    (net (code "147") (name "unconnected-(CM4K-WL_nDisable-Pad89)") (class "Default")
      (node (ref "CM4") (pin "89") (pinfunction "WL_nDisable_89") (pintype "input+no_connect"))
    )
    (net (code "148") (name "unconnected-(CM4L-PI_LED_nPWR-Pad95)") (class "Default")
      (node (ref "CM4") (pin "95") (pinfunction "PI_LED_nPWR_95") (pintype "output"))
    )
    (net (code "149") (name "unconnected-(CM4L-Pi_nLED_Activity-Pad21)") (class "Default")
      (node (ref "CM4") (pin "21") (pinfunction "Pi_nLED_Activity_21") (pintype "open_collector"))
    )
    (net (code "150") (name "unconnected-(CM4M-AnalogIP0-Pad96)") (class "Default")
      (node (ref "CM4") (pin "96") (pinfunction "AnalogIP0_96") (pintype "passive"))
    )
    (net (code "151") (name "unconnected-(CM4M-AnalogIP1-Pad94)") (class "Default")
      (node (ref "CM4") (pin "94") (pinfunction "AnalogIP1_94") (pintype "passive"))
    )
    (net (code "152") (name "unconnected-(CM4M-GLOBAL_EN-Pad99)") (class "Default")
      (node (ref "CM4") (pin "99") (pinfunction "GLOBAL_EN_99") (pintype "input"))
    )
    (net (code "153") (name "unconnected-(CM4M-RUN_PG-Pad92)") (class "Default")
      (node (ref "CM4") (pin "92") (pinfunction "RUN_PG_92") (pintype "passive"))
    )
    (net (code "154") (name "unconnected-(CM4M-nEXTRST-Pad100)") (class "Default")
      (node (ref "CM4") (pin "100") (pinfunction "nEXTRST_100") (pintype "output"))
    )
    (net (code "155") (name "unconnected-(CM4M-nRPIBOOT-Pad93)") (class "Default")
      (node (ref "CM4") (pin "93") (pinfunction "nRPIBOOT_93") (pintype "input"))
    )
    (net (code "156") (name "unconnected-(CM4N-USB_N-Pad103)") (class "Default")
      (node (ref "CM4") (pin "103") (pinfunction "USB_N_103") (pintype "passive"))
    )
    (net (code "157") (name "unconnected-(CM4N-USB_OTG_ID-Pad101)") (class "Default")
      (node (ref "CM4") (pin "101") (pinfunction "USB_OTG_ID_101") (pintype "input"))
    )
    (net (code "158") (name "unconnected-(CM4N-USB_P-Pad105)") (class "Default")
      (node (ref "CM4") (pin "105") (pinfunction "USB_P_105") (pintype "passive"))
    )
    (net (code "159") (name "unconnected-(CM4O-EEPROM_nWP-Pad20)") (class "Default")
      (node (ref "CM4") (pin "20") (pinfunction "EEPROM_nWP_20") (pintype "passive+no_connect"))
    )
    (net (code "160") (name "unconnected-(CM4O-Reserved-Pad76)") (class "Default")
      (node (ref "CM4") (pin "76") (pinfunction "Reserved_76") (pintype "passive+no_connect"))
    )
    (net (code "161") (name "unconnected-(CM4O-Reserved-Pad104)") (class "Default")
      (node (ref "CM4") (pin "104") (pinfunction "Reserved_104") (pintype "passive+no_connect"))
    )
    (net (code "162") (name "unconnected-(CM4O-Reserved-Pad106)") (class "Default")
      (node (ref "CM4") (pin "106") (pinfunction "Reserved_106") (pintype "passive+no_connect"))
    )
    (net (code "163") (name "unconnected-(CM4P-Ethernet_SYNC_IN-Pad16)") (class "Default")
      (node (ref "CM4") (pin "16") (pinfunction "Ethernet_SYNC_IN_16") (pintype "input+no_connect"))
    )
    (net (code "164") (name "unconnected-(CM4P-Ethernet_SYNC_OUT-Pad18)") (class "Default")
      (node (ref "CM4") (pin "18") (pinfunction "Ethernet_SYNC_OUT_18") (pintype "input+no_connect"))
    )
    (net (code "165") (name "unconnected-(CM4P-Ethernet_nLED1-Pad19)") (class "Default")
      (node (ref "CM4") (pin "19") (pinfunction "Ethernet_nLED1_19") (pintype "output+no_connect"))
    )
    (net (code "166") (name "unconnected-(CM4Q-CM4_1.8V_(Output)-Pad88)") (class "Default")
      (node (ref "CM4") (pin "88") (pinfunction "CM4_1.8V_(Output)_88") (pintype "power_in+no_connect"))
    )
    (net (code "167") (name "unconnected-(CM4Q-CM4_1.8V_(Output)-Pad90)") (class "Default")
      (node (ref "CM4") (pin "90") (pinfunction "CM4_1.8V_(Output)_90") (pintype "power_in+no_connect"))
    )
    (net (code "168") (name "unconnected-(CM4Q-CM4_3.3V_(Output)-Pad84)") (class "Default")
      (node (ref "CM4") (pin "84") (pinfunction "CM4_3.3V_(Output)_84") (pintype "power_in+no_connect"))
    )
    (net (code "169") (name "unconnected-(CM4Q-CM4_3.3V_(Output)-Pad86)") (class "Default")
      (node (ref "CM4") (pin "86") (pinfunction "CM4_3.3V_(Output)_86") (pintype "power_in+no_connect"))
    )
    (net (code "170") (name "unconnected-(CM4R-I2C_SCL0-Pad80)") (class "Default")
      (node (ref "CM4") (pin "80") (pinfunction "I2C_SCL0_80") (pintype "passive"))
    )
    (net (code "171") (name "unconnected-(CM4R-I2C_SDA0-Pad82)") (class "Default")
      (node (ref "CM4") (pin "82") (pinfunction "I2C_SDA0_82") (pintype "passive"))
    )
    (net (code "172") (name "unconnected-(CM4S-ID_SC-Pad35)") (class "Default")
      (node (ref "CM4") (pin "35") (pinfunction "ID_SC_35") (pintype "passive"))
    )
    (net (code "173") (name "unconnected-(CM4S-ID_SD-Pad36)") (class "Default")
      (node (ref "CM4") (pin "36") (pinfunction "ID_SD_36") (pintype "passive"))
    )
    (net (code "174") (name "unconnected-(CM4T-Camera_GPIO-Pad97)") (class "Default")
      (node (ref "CM4") (pin "97") (pinfunction "Camera_GPIO_97") (pintype "passive"))
    )
    (net (code "175") (name "unconnected-(CM4U-GPIO12-Pad31)") (class "Default")
      (node (ref "CM4") (pin "31") (pinfunction "GPIO12_31") (pintype "passive"))
    )
    (net (code "176") (name "unconnected-(CM4U-GPIO13-Pad28)") (class "Default")
      (node (ref "CM4") (pin "28") (pinfunction "GPIO13_28") (pintype "passive"))
    )
    (net (code "177") (name "unconnected-(CM4U-VDAC_COMP-Pad111)") (class "Default")
      (node (ref "CM4") (pin "111") (pinfunction "VDAC_COMP_111") (pintype "passive"))
    )
    (net (code "178") (name "unconnected-(DRV1-NC-Pad16)") (class "Default")
      (node (ref "DRV1") (pin "16") (pinfunction "NC_16") (pintype "passive+no_connect"))
    )
    (net (code "179") (name "unconnected-(DRV2-NC-Pad16)") (class "Default")
      (node (ref "DRV2") (pin "16") (pinfunction "NC_16") (pintype "passive+no_connect"))
    )
    (net (code "180") (name "unconnected-(IC1-NRST-Pad7)") (class "Default")
      (node (ref "IC1") (pin "7") (pinfunction "NRST_7") (pintype "passive"))
    )
    (net (code "181") (name "unconnected-(IC1-PA0-Pad14)") (class "Default")
      (node (ref "IC1") (pin "14") (pinfunction "PA0_14") (pintype "passive"))
    )
    (net (code "182") (name "unconnected-(IC1-PA1-Pad15)") (class "Default")
      (node (ref "IC1") (pin "15") (pinfunction "PA1_15") (pintype "passive"))
    )
    (net (code "183") (name "unconnected-(IC1-PA2-Pad16)") (class "Default")
      (node (ref "IC1") (pin "16") (pinfunction "PA2_16") (pintype "passive"))
    )
    (net (code "184") (name "unconnected-(IC1-PA3-Pad17)") (class "Default")
      (node (ref "IC1") (pin "17") (pinfunction "PA3_17") (pintype "passive"))
    )
    (net (code "185") (name "unconnected-(IC1-PA4-Pad20)") (class "Default")
      (node (ref "IC1") (pin "20") (pinfunction "PA4_20") (pintype "passive"))
    )
    (net (code "186") (name "unconnected-(IC1-PA5-Pad21)") (class "Default")
      (node (ref "IC1") (pin "21") (pinfunction "PA5_21") (pintype "passive"))
    )
    (net (code "187") (name "unconnected-(IC1-PA6-Pad22)") (class "Default")
      (node (ref "IC1") (pin "22") (pinfunction "PA6_22") (pintype "passive"))
    )
    (net (code "188") (name "unconnected-(IC1-PA7-Pad23)") (class "Default")
      (node (ref "IC1") (pin "23") (pinfunction "PA7_23") (pintype "passive"))
    )
    (net (code "189") (name "unconnected-(IC1-PA8-Pad41)") (class "Default")
      (node (ref "IC1") (pin "41") (pinfunction "PA8_41") (pintype "passive"))
    )
    (net (code "190") (name "unconnected-(IC1-PA9-Pad42)") (class "Default")
      (node (ref "IC1") (pin "42") (pinfunction "PA9_42") (pintype "passive"))
    )
    (net (code "191") (name "unconnected-(IC1-PA10-Pad43)") (class "Default")
      (node (ref "IC1") (pin "43") (pinfunction "PA10_43") (pintype "passive"))
    )
    (net (code "192") (name "unconnected-(IC1-PA11-Pad44)") (class "Default")
      (node (ref "IC1") (pin "44") (pinfunction "PA11_44") (pintype "passive"))
    )
    (net (code "193") (name "unconnected-(IC1-PA12-Pad45)") (class "Default")
      (node (ref "IC1") (pin "45") (pinfunction "PA12_45") (pintype "passive"))
    )
    (net (code "194") (name "unconnected-(IC1-PA13-Pad46)") (class "Default")
      (node (ref "IC1") (pin "46") (pinfunction "PA13_46") (pintype "passive"))
    )
    (net (code "195") (name "unconnected-(IC1-PA14-Pad49)") (class "Default")
      (node (ref "IC1") (pin "49") (pinfunction "PA14_49") (pintype "passive"))
    )
    (net (code "196") (name "unconnected-(IC1-PA15-Pad50)") (class "Default")
      (node (ref "IC1") (pin "50") (pinfunction "PA15_50") (pintype "passive"))
    )
    (net (code "197") (name "unconnected-(IC1-PB0-Pad26)") (class "Default")
      (node (ref "IC1") (pin "26") (pinfunction "PB0_26") (pintype "passive"))
    )
    (net (code "198") (name "unconnected-(IC1-PB1-Pad27)") (class "Default")
      (node (ref "IC1") (pin "27") (pinfunction "PB1_27") (pintype "passive"))
    )
    (net (code "199") (name "unconnected-(IC1-PB2-Pad28)") (class "Default")
      (node (ref "IC1") (pin "28") (pinfunction "PB2_28") (pintype "passive"))
    )
    (net (code "200") (name "unconnected-(IC1-PB3-Pad55)") (class "Default")
      (node (ref "IC1") (pin "55") (pinfunction "PB3_55") (pintype "passive"))
    )
    (net (code "201") (name "unconnected-(IC1-PB4-Pad56)") (class "Default")
      (node (ref "IC1") (pin "56") (pinfunction "PB4_56") (pintype "passive"))
    )
    (net (code "202") (name "unconnected-(IC1-PB5-Pad57)") (class "Default")
      (node (ref "IC1") (pin "57") (pinfunction "PB5_57") (pintype "passive"))
    )
    (net (code "203") (name "unconnected-(IC1-PB6-Pad58)") (class "Default")
      (node (ref "IC1") (pin "58") (pinfunction "PB6_58") (pintype "passive"))
    )
    (net (code "204") (name "unconnected-(IC1-PB7-Pad59)") (class "Default")
      (node (ref "IC1") (pin "59") (pinfunction "PB7_59") (pintype "passive"))
    )
    (net (code "205") (name "unconnected-(IC1-PB8-Pad61)") (class "Default")
      (node (ref "IC1") (pin "61") (pinfunction "PB8_61") (pintype "passive"))
    )
    (net (code "206") (name "unconnected-(IC1-PB9-Pad62)") (class "Default")
      (node (ref "IC1") (pin "62") (pinfunction "PB9_62") (pintype "passive"))
    )
    (net (code "207") (name "unconnected-(IC1-PB10-Pad29)") (class "Default")
      (node (ref "IC1") (pin "29") (pinfunction "PB10_29") (pintype "passive"))
    )
    (net (code "208") (name "unconnected-(IC1-PB11-Pad30)") (class "Default")
      (node (ref "IC1") (pin "30") (pinfunction "PB11_30") (pintype "passive"))
    )
    (net (code "209") (name "unconnected-(IC1-PB12-Pad33)") (class "Default")
      (node (ref "IC1") (pin "33") (pinfunction "PB12_33") (pintype "passive"))
    )
    (net (code "210") (name "unconnected-(IC1-PB13-Pad34)") (class "Default")
      (node (ref "IC1") (pin "34") (pinfunction "PB13_34") (pintype "passive"))
    )
    (net (code "211") (name "unconnected-(IC1-PB14-Pad35)") (class "Default")
      (node (ref "IC1") (pin "35") (pinfunction "PB14_35") (pintype "passive"))
    )
    (net (code "212") (name "unconnected-(IC1-PB15-Pad36)") (class "Default")
      (node (ref "IC1") (pin "36") (pinfunction "PB15_36") (pintype "passive"))
    )
    (net (code "213") (name "unconnected-(IC1-PC0-Pad8)") (class "Default")
      (node (ref "IC1") (pin "8") (pinfunction "PC0_8") (pintype "passive"))
    )
    (net (code "214") (name "unconnected-(IC1-PC1-Pad9)") (class "Default")
      (node (ref "IC1") (pin "9") (pinfunction "PC1_9") (pintype "passive"))
    )
    (net (code "215") (name "unconnected-(IC1-PC2-Pad10)") (class "Default")
      (node (ref "IC1") (pin "10") (pinfunction "PC2_10") (pintype "passive"))
    )
    (net (code "216") (name "unconnected-(IC1-PC3-Pad11)") (class "Default")
      (node (ref "IC1") (pin "11") (pinfunction "PC3_11") (pintype "passive"))
    )
    (net (code "217") (name "unconnected-(IC1-PC4-Pad24)") (class "Default")
      (node (ref "IC1") (pin "24") (pinfunction "PC4_24") (pintype "passive"))
    )
    (net (code "218") (name "unconnected-(IC1-PC5-Pad25)") (class "Default")
      (node (ref "IC1") (pin "25") (pinfunction "PC5_25") (pintype "passive"))
    )
    (net (code "219") (name "unconnected-(IC1-PC6-Pad37)") (class "Default")
      (node (ref "IC1") (pin "37") (pinfunction "PC6_37") (pintype "passive"))
    )
    (net (code "220") (name "unconnected-(IC1-PC7-Pad38)") (class "Default")
      (node (ref "IC1") (pin "38") (pinfunction "PC7_38") (pintype "passive"))
    )
    (net (code "221") (name "unconnected-(IC1-PC8-Pad39)") (class "Default")
      (node (ref "IC1") (pin "39") (pinfunction "PC8_39") (pintype "passive"))
    )
    (net (code "222") (name "unconnected-(IC1-PC9-Pad40)") (class "Default")
      (node (ref "IC1") (pin "40") (pinfunction "PC9_40") (pintype "passive"))
    )
    (net (code "223") (name "unconnected-(IC1-PC10-Pad51)") (class "Default")
      (node (ref "IC1") (pin "51") (pinfunction "PC10_51") (pintype "passive"))
    )
    (net (code "224") (name "unconnected-(IC1-PC11-Pad52)") (class "Default")
      (node (ref "IC1") (pin "52") (pinfunction "PC11_52") (pintype "passive"))
    )
    (net (code "225") (name "unconnected-(IC1-PC12-Pad53)") (class "Default")
      (node (ref "IC1") (pin "53") (pinfunction "PC12_53") (pintype "passive"))
    )
    (net (code "226") (name "unconnected-(IC1-PC13-Pad2)") (class "Default")
      (node (ref "IC1") (pin "2") (pinfunction "PC13_2") (pintype "passive"))
    )
    (net (code "227") (name "unconnected-(IC1-PD2-Pad54)") (class "Default")
      (node (ref "IC1") (pin "54") (pinfunction "PD2_54") (pintype "passive"))
    )
  )
)
